# GEVCU-4.net
KiCad netlist of a schematic drawn in EAGLE
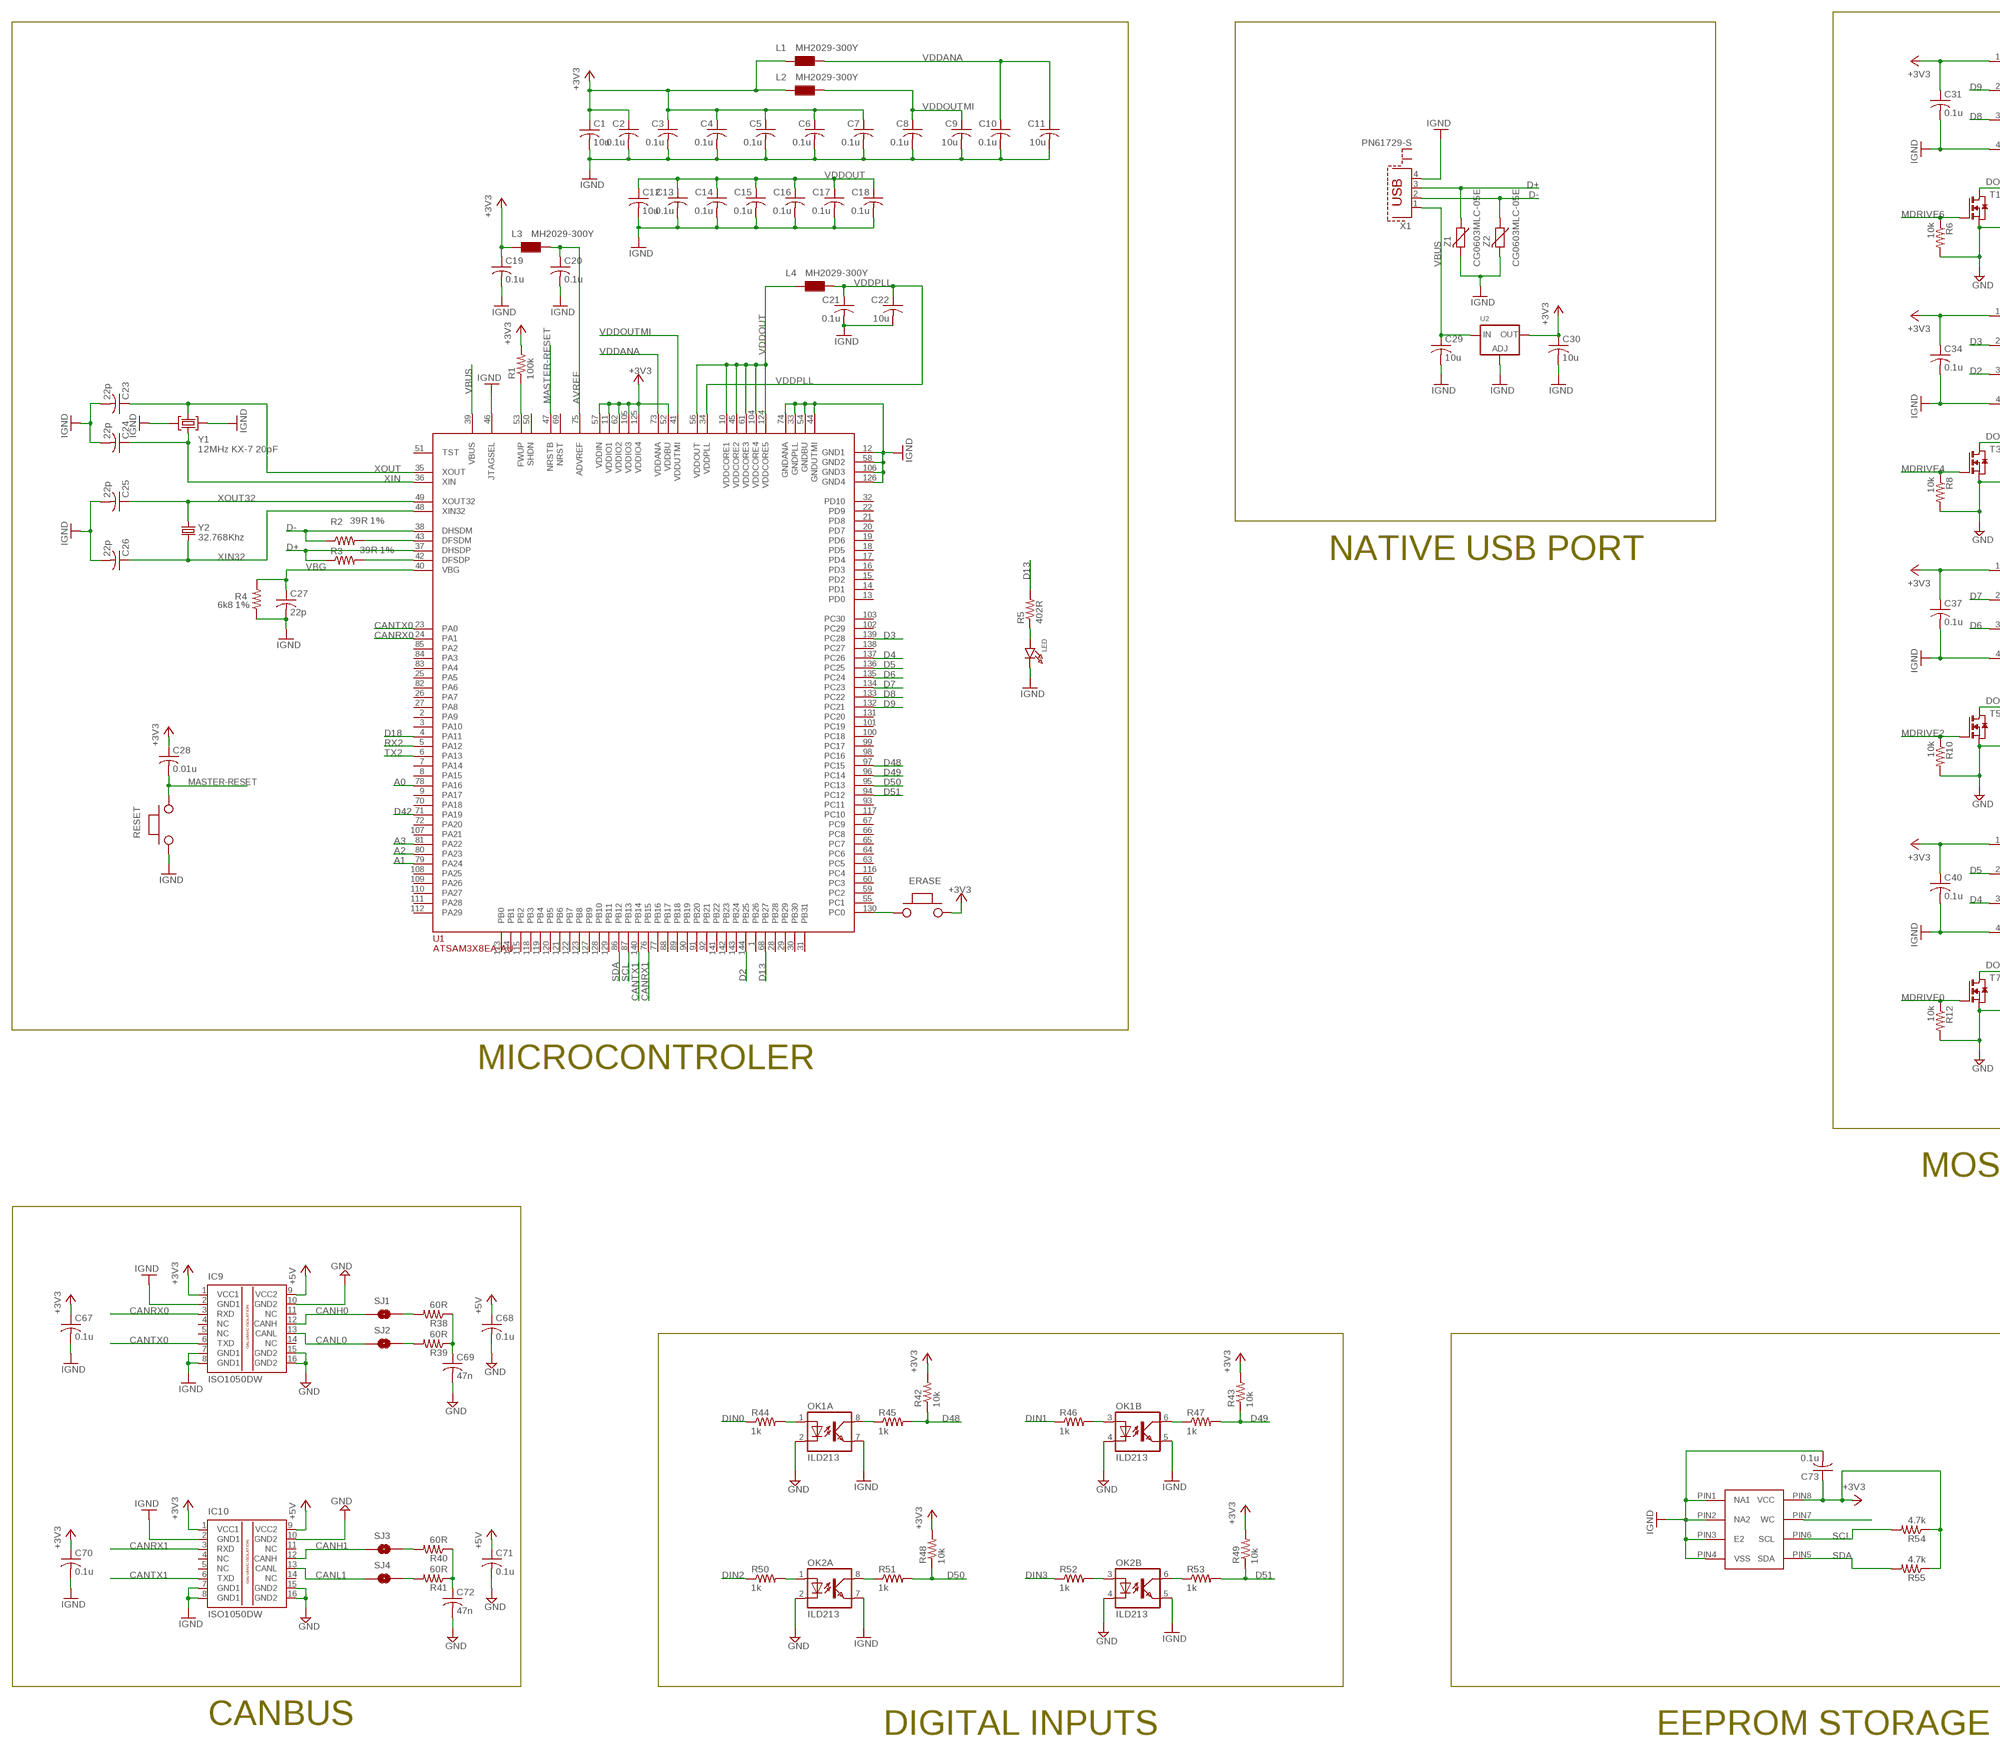
[diagram p0: schematic, sheet 1, part 1 of 2]
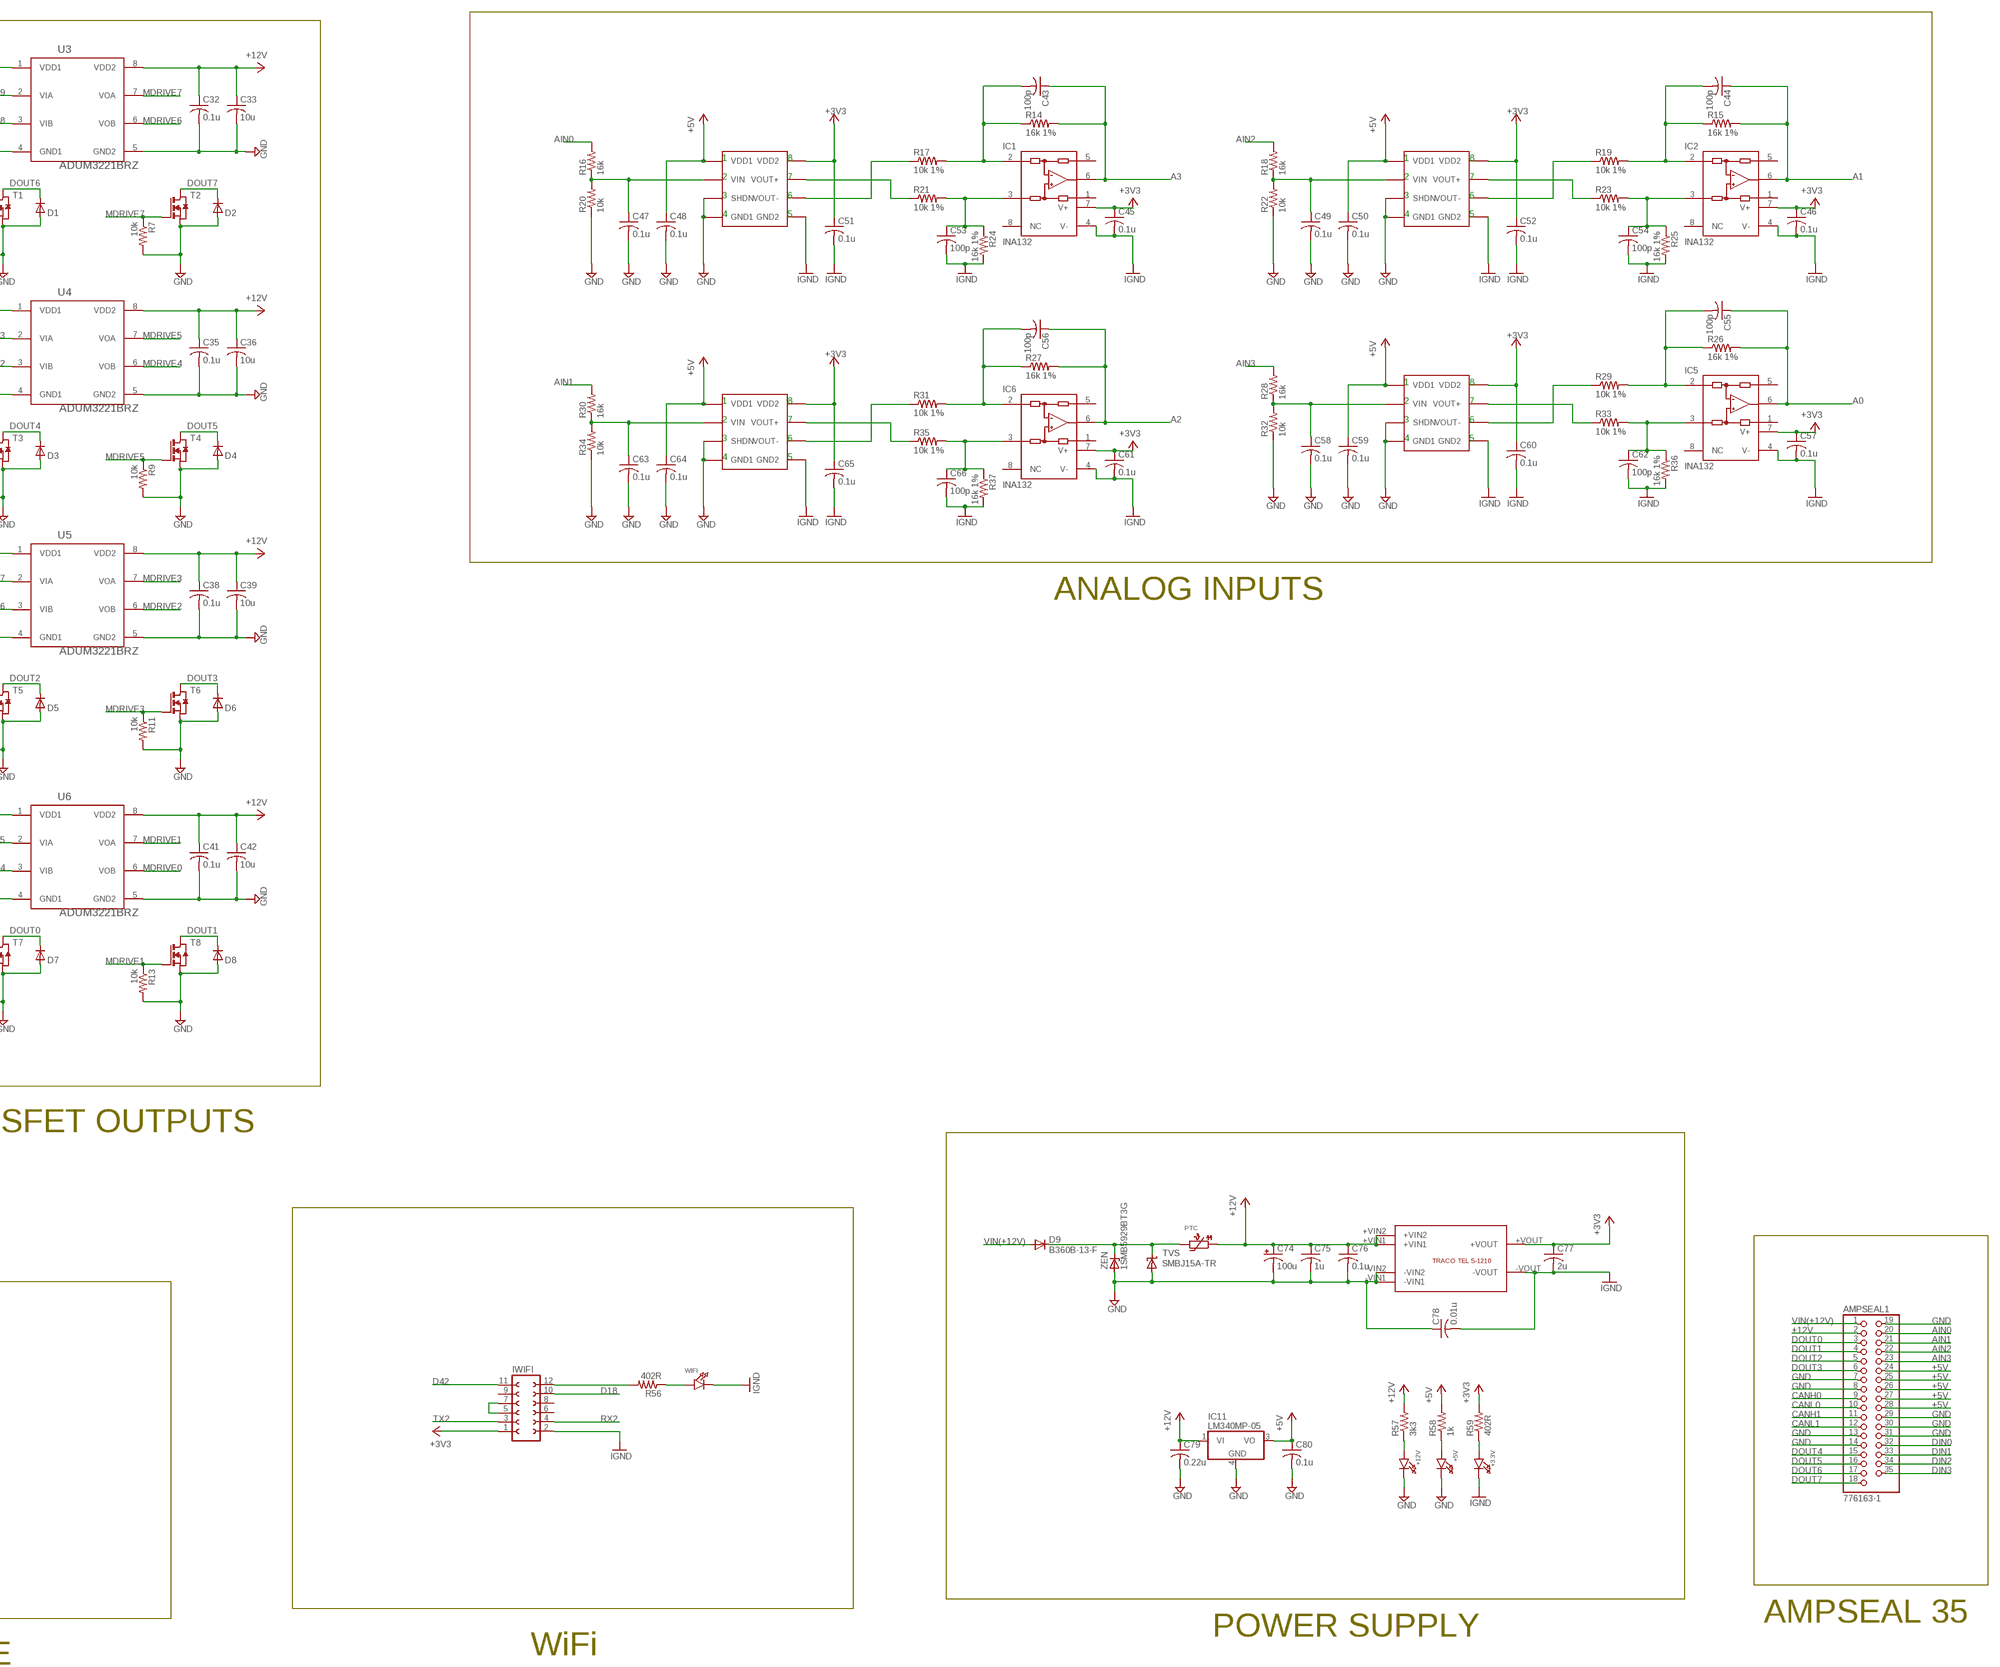
[diagram p1: schematic, sheet 1, part 2 of 2]

(export (version "E")
  (design (tool "Eeschema 10.0.6"))
  (components
    (comp (ref "+3.3V")
      (value "LED0805")
      (footprint "eagle-import:CHIPLED_0805")
      (libsource (lib "eagle-import") (part "LED0805"))
    )
    (comp (ref "+5V")
      (value "LED0805")
      (footprint "eagle-import:CHIPLED_0805")
      (libsource (lib "eagle-import") (part "LED0805"))
    )
    (comp (ref "+12V")
      (value "LED0805")
      (footprint "eagle-import:CHIPLED_0805")
      (libsource (lib "eagle-import") (part "LED0805"))
    )
    (comp (ref "AMPSEAL1")
      (value "776163-1")
      (footprint "eagle-import:AMPSEAL35")
      (libsource (lib "eagle-import") (part "AMPSEAL35"))
    )
    (comp (ref "C1")
      (value "10u")
      (footprint "eagle-import:C0805")
      (libsource (lib "eagle-import") (part "C-USC0805"))
    )
    (comp (ref "C2")
      (value "0.1u")
      (footprint "eagle-import:C0805")
      (libsource (lib "eagle-import") (part "C-USC0805"))
    )
    (comp (ref "C3")
      (value "0.1u")
      (footprint "eagle-import:C0805")
      (libsource (lib "eagle-import") (part "C-USC0805"))
    )
    (comp (ref "C4")
      (value "0.1u")
      (footprint "eagle-import:C0805")
      (libsource (lib "eagle-import") (part "C-USC0805"))
    )
    (comp (ref "C5")
      (value "0.1u")
      (footprint "eagle-import:C0805")
      (libsource (lib "eagle-import") (part "C-USC0805"))
    )
    (comp (ref "C6")
      (value "0.1u")
      (footprint "eagle-import:C0805")
      (libsource (lib "eagle-import") (part "C-USC0805"))
    )
    (comp (ref "C7")
      (value "0.1u")
      (footprint "eagle-import:C0805")
      (libsource (lib "eagle-import") (part "C-USC0805"))
    )
    (comp (ref "C8")
      (value "0.1u")
      (footprint "eagle-import:C0805")
      (libsource (lib "eagle-import") (part "C-USC0805"))
    )
    (comp (ref "C9")
      (value "10u")
      (footprint "eagle-import:C0805")
      (libsource (lib "eagle-import") (part "C-USC0805"))
    )
    (comp (ref "C10")
      (value "0.1u")
      (footprint "eagle-import:C0805")
      (libsource (lib "eagle-import") (part "C-USC0805"))
    )
    (comp (ref "C11")
      (value "10u")
      (footprint "eagle-import:C0805")
      (libsource (lib "eagle-import") (part "C-USC0805"))
    )
    (comp (ref "C12")
      (value "10u")
      (footprint "eagle-import:C0805")
      (libsource (lib "eagle-import") (part "C-USC0805"))
    )
    (comp (ref "C13")
      (value "0.1u")
      (footprint "eagle-import:C0805")
      (libsource (lib "eagle-import") (part "C-USC0805"))
    )
    (comp (ref "C14")
      (value "0.1u")
      (footprint "eagle-import:C0805")
      (libsource (lib "eagle-import") (part "C-USC0805"))
    )
    (comp (ref "C15")
      (value "0.1u")
      (footprint "eagle-import:C0805")
      (libsource (lib "eagle-import") (part "C-USC0805"))
    )
    (comp (ref "C16")
      (value "0.1u")
      (footprint "eagle-import:C0805")
      (libsource (lib "eagle-import") (part "C-USC0805"))
    )
    (comp (ref "C17")
      (value "0.1u")
      (footprint "eagle-import:C0805")
      (libsource (lib "eagle-import") (part "C-USC0805"))
    )
    (comp (ref "C18")
      (value "0.1u")
      (footprint "eagle-import:C0805")
      (libsource (lib "eagle-import") (part "C-USC0805"))
    )
    (comp (ref "C19")
      (value "0.1u")
      (footprint "eagle-import:C0805")
      (libsource (lib "eagle-import") (part "C-USC0805"))
    )
    (comp (ref "C20")
      (value "0.1u")
      (footprint "eagle-import:C0805")
      (libsource (lib "eagle-import") (part "C-USC0805"))
    )
    (comp (ref "C21")
      (value "0.1u")
      (footprint "eagle-import:C0805")
      (libsource (lib "eagle-import") (part "C-USC0805"))
    )
    (comp (ref "C22")
      (value "10u")
      (footprint "eagle-import:C0805")
      (libsource (lib "eagle-import") (part "C-USC0805"))
    )
    (comp (ref "C23")
      (value "22p")
      (footprint "eagle-import:C1206")
      (libsource (lib "eagle-import") (part "C-USC1206"))
    )
    (comp (ref "C24")
      (value "22p")
      (footprint "eagle-import:C1206")
      (libsource (lib "eagle-import") (part "C-USC1206"))
    )
    (comp (ref "C25")
      (value "22p")
      (footprint "eagle-import:C0805")
      (libsource (lib "eagle-import") (part "C-USC0805"))
    )
    (comp (ref "C26")
      (value "22p")
      (footprint "eagle-import:C0805")
      (libsource (lib "eagle-import") (part "C-USC0805"))
    )
    (comp (ref "C27")
      (value "22p")
      (footprint "eagle-import:C0805")
      (libsource (lib "eagle-import") (part "C-USC0805"))
    )
    (comp (ref "C28")
      (value "0.01u")
      (footprint "eagle-import:C0805")
      (libsource (lib "eagle-import") (part "C-USC0805"))
    )
    (comp (ref "C29")
      (value "10u")
      (footprint "eagle-import:C0805")
      (libsource (lib "eagle-import") (part "C-USC0805"))
    )
    (comp (ref "C30")
      (value "10u")
      (footprint "eagle-import:C0805")
      (libsource (lib "eagle-import") (part "C-USC0805"))
    )
    (comp (ref "C31")
      (value "0.1u")
      (footprint "eagle-import:C0805")
      (libsource (lib "eagle-import") (part "C-USC0805"))
    )
    (comp (ref "C32")
      (value "0.1u")
      (footprint "eagle-import:C0805")
      (libsource (lib "eagle-import") (part "C-USC0805"))
    )
    (comp (ref "C33")
      (value "10u")
      (footprint "eagle-import:C0805")
      (libsource (lib "eagle-import") (part "C-USC0805"))
    )
    (comp (ref "C34")
      (value "0.1u")
      (footprint "eagle-import:C0805")
      (libsource (lib "eagle-import") (part "C-USC0805"))
    )
    (comp (ref "C35")
      (value "0.1u")
      (footprint "eagle-import:C0805")
      (libsource (lib "eagle-import") (part "C-USC0805"))
    )
    (comp (ref "C36")
      (value "10u")
      (footprint "eagle-import:C0805")
      (libsource (lib "eagle-import") (part "C-USC0805"))
    )
    (comp (ref "C37")
      (value "0.1u")
      (footprint "eagle-import:C0805")
      (libsource (lib "eagle-import") (part "C-USC0805"))
    )
    (comp (ref "C38")
      (value "0.1u")
      (footprint "eagle-import:C0805")
      (libsource (lib "eagle-import") (part "C-USC0805"))
    )
    (comp (ref "C39")
      (value "10u")
      (footprint "eagle-import:C0805")
      (libsource (lib "eagle-import") (part "C-USC0805"))
    )
    (comp (ref "C40")
      (value "0.1u")
      (footprint "eagle-import:C0805")
      (libsource (lib "eagle-import") (part "C-USC0805"))
    )
    (comp (ref "C41")
      (value "0.1u")
      (footprint "eagle-import:C0805")
      (libsource (lib "eagle-import") (part "C-USC0805"))
    )
    (comp (ref "C42")
      (value "10u")
      (footprint "eagle-import:C0805")
      (libsource (lib "eagle-import") (part "C-USC0805"))
    )
    (comp (ref "C43")
      (value "100p")
      (footprint "eagle-import:C0805")
      (libsource (lib "eagle-import") (part "C-USC0805"))
    )
    (comp (ref "C44")
      (value "100p")
      (footprint "eagle-import:C0805")
      (libsource (lib "eagle-import") (part "C-USC0805"))
    )
    (comp (ref "C45")
      (value "0.1u")
      (footprint "eagle-import:C0805")
      (libsource (lib "eagle-import") (part "C-USC0805"))
    )
    (comp (ref "C46")
      (value "0.1u")
      (footprint "eagle-import:C0805")
      (libsource (lib "eagle-import") (part "C-USC0805"))
    )
    (comp (ref "C47")
      (value "0.1u")
      (footprint "eagle-import:C0805")
      (libsource (lib "eagle-import") (part "C-USC0805"))
    )
    (comp (ref "C48")
      (value "0.1u")
      (footprint "eagle-import:C1206")
      (libsource (lib "eagle-import") (part "C-USC1206"))
    )
    (comp (ref "C49")
      (value "0.1u")
      (footprint "eagle-import:C0805")
      (libsource (lib "eagle-import") (part "C-USC0805"))
    )
    (comp (ref "C50")
      (value "0.1u")
      (footprint "eagle-import:C1206")
      (libsource (lib "eagle-import") (part "C-USC1206"))
    )
    (comp (ref "C51")
      (value "0.1u")
      (footprint "eagle-import:C0805")
      (libsource (lib "eagle-import") (part "C-USC0805"))
    )
    (comp (ref "C52")
      (value "0.1u")
      (footprint "eagle-import:C0805")
      (libsource (lib "eagle-import") (part "C-USC0805"))
    )
    (comp (ref "C53")
      (value "100p")
      (footprint "eagle-import:C0805")
      (libsource (lib "eagle-import") (part "C-USC0805"))
    )
    (comp (ref "C54")
      (value "100p")
      (footprint "eagle-import:C0805")
      (libsource (lib "eagle-import") (part "C-USC0805"))
    )
    (comp (ref "C55")
      (value "100p")
      (footprint "eagle-import:C0805")
      (libsource (lib "eagle-import") (part "C-USC0805"))
    )
    (comp (ref "C56")
      (value "100p")
      (footprint "eagle-import:C0805")
      (libsource (lib "eagle-import") (part "C-USC0805"))
    )
    (comp (ref "C57")
      (value "0.1u")
      (footprint "eagle-import:C0805")
      (libsource (lib "eagle-import") (part "C-USC0805"))
    )
    (comp (ref "C58")
      (value "0.1u")
      (footprint "eagle-import:C0805")
      (libsource (lib "eagle-import") (part "C-USC0805"))
    )
    (comp (ref "C59")
      (value "0.1u")
      (footprint "eagle-import:C1206")
      (libsource (lib "eagle-import") (part "C-USC1206"))
    )
    (comp (ref "C60")
      (value "0.1u")
      (footprint "eagle-import:C0805")
      (libsource (lib "eagle-import") (part "C-USC0805"))
    )
    (comp (ref "C61")
      (value "0.1u")
      (footprint "eagle-import:C0805")
      (libsource (lib "eagle-import") (part "C-USC0805"))
    )
    (comp (ref "C62")
      (value "100p")
      (footprint "eagle-import:C0805")
      (libsource (lib "eagle-import") (part "C-USC0805"))
    )
    (comp (ref "C63")
      (value "0.1u")
      (footprint "eagle-import:C0805")
      (libsource (lib "eagle-import") (part "C-USC0805"))
    )
    (comp (ref "C64")
      (value "0.1u")
      (footprint "eagle-import:C1206")
      (libsource (lib "eagle-import") (part "C-USC1206"))
    )
    (comp (ref "C65")
      (value "0.1u")
      (footprint "eagle-import:C0805")
      (libsource (lib "eagle-import") (part "C-USC0805"))
    )
    (comp (ref "C66")
      (value "100p")
      (footprint "eagle-import:C0805")
      (libsource (lib "eagle-import") (part "C-USC0805"))
    )
    (comp (ref "C67")
      (value "0.1u")
      (footprint "eagle-import:C0805")
      (libsource (lib "eagle-import") (part "C-USC0805"))
    )
    (comp (ref "C68")
      (value "0.1u")
      (footprint "eagle-import:C0805")
      (libsource (lib "eagle-import") (part "C-USC0805"))
    )
    (comp (ref "C69")
      (value "47n")
      (footprint "eagle-import:C0805")
      (libsource (lib "eagle-import") (part "C-USC0805"))
    )
    (comp (ref "C70")
      (value "0.1u")
      (footprint "eagle-import:C0805")
      (libsource (lib "eagle-import") (part "C-USC0805"))
    )
    (comp (ref "C71")
      (value "0.1u")
      (footprint "eagle-import:C0805")
      (libsource (lib "eagle-import") (part "C-USC0805"))
    )
    (comp (ref "C72")
      (value "47n")
      (footprint "eagle-import:C0805")
      (libsource (lib "eagle-import") (part "C-USC0805"))
    )
    (comp (ref "C73")
      (value "0.1u")
      (footprint "eagle-import:C0805")
      (libsource (lib "eagle-import") (part "C-USC0805"))
    )
    (comp (ref "C74")
      (value "100u")
      (footprint "eagle-import:E2,5-6")
      (libsource (lib "eagle-import") (part "CPOL-USE2.5-6"))
    )
    (comp (ref "C75")
      (value "1u")
      (footprint "eagle-import:C0805")
      (libsource (lib "eagle-import") (part "C-USC0805"))
    )
    (comp (ref "C76")
      (value "0.1u")
      (footprint "eagle-import:C0805")
      (libsource (lib "eagle-import") (part "C-USC0805"))
    )
    (comp (ref "C77")
      (value "2u")
      (footprint "eagle-import:C0805")
      (libsource (lib "eagle-import") (part "C-USC0805"))
    )
    (comp (ref "C78")
      (value "0.01u")
      (footprint "eagle-import:C1812")
      (libsource (lib "eagle-import") (part "C-USC1812"))
    )
    (comp (ref "C79")
      (value "0.22u")
      (footprint "eagle-import:C0805")
      (libsource (lib "eagle-import") (part "C-USC0805"))
    )
    (comp (ref "C80")
      (value "0.1u")
      (footprint "eagle-import:C0805")
      (libsource (lib "eagle-import") (part "C-USC0805"))
    )
    (comp (ref "D1")
      (value "MBR0520LT")
      (footprint "eagle-import:SOD123")
      (libsource (lib "eagle-import") (part "MBR0520LT"))
    )
    (comp (ref "D2")
      (value "MBR0520LT")
      (footprint "eagle-import:SOD123")
      (libsource (lib "eagle-import") (part "MBR0520LT"))
    )
    (comp (ref "D3")
      (value "MBR0520LT")
      (footprint "eagle-import:SOD123")
      (libsource (lib "eagle-import") (part "MBR0520LT"))
    )
    (comp (ref "D4")
      (value "MBR0520LT")
      (footprint "eagle-import:SOD123")
      (libsource (lib "eagle-import") (part "MBR0520LT"))
    )
    (comp (ref "D5")
      (value "MBR0520LT")
      (footprint "eagle-import:SOD123")
      (libsource (lib "eagle-import") (part "MBR0520LT"))
    )
    (comp (ref "D6")
      (value "MBR0520LT")
      (footprint "eagle-import:SOD123")
      (libsource (lib "eagle-import") (part "MBR0520LT"))
    )
    (comp (ref "D7")
      (value "MBR0520LT")
      (footprint "eagle-import:SOD123")
      (libsource (lib "eagle-import") (part "MBR0520LT"))
    )
    (comp (ref "D8")
      (value "MBR0520LT")
      (footprint "eagle-import:SOD123")
      (libsource (lib "eagle-import") (part "MBR0520LT"))
    )
    (comp (ref "D9")
      (value "B360B-13-F")
      (footprint "eagle-import:SMB")
      (libsource (lib "eagle-import") (part "DIODE-SMB"))
    )
    (comp (ref "ERASE")
      (value "PUCHBUTTON")
      (footprint "eagle-import:PUCHBUTTON")
      (libsource (lib "eagle-import") (part "PUCHBUTTON"))
    )
    (comp (ref "IC1")
      (value "INA132")
      (footprint "eagle-import:SO08")
      (fields (field (name "MF") "TEXAS INSTRUMENTS") (field (name "MPN") "INA105KU"))
      (libsource (lib "eagle-import") (part "INA105U"))
    )
    (comp (ref "IC2")
      (value "INA132")
      (footprint "eagle-import:SO08")
      (fields (field (name "MF") "TEXAS INSTRUMENTS") (field (name "MPN") "INA105KU"))
      (libsource (lib "eagle-import") (part "INA105U"))
    )
    (comp (ref "IC3")
      (value "CK_CUSTOM_ACPL-C87A-000E")
      (footprint "eagle-import:CK_CUSTOM_SO8-WIDE")
      (libsource (lib "eagle-import") (part "CK_CUSTOM_ACPL-C87A-000E"))
    )
    (comp (ref "IC4")
      (value "CK_CUSTOM_ACPL-C87A-000E")
      (footprint "eagle-import:CK_CUSTOM_SO8-WIDE")
      (libsource (lib "eagle-import") (part "CK_CUSTOM_ACPL-C87A-000E"))
    )
    (comp (ref "IC5")
      (value "INA132")
      (footprint "eagle-import:SO08")
      (fields (field (name "MF") "TEXAS INSTRUMENTS") (field (name "MPN") "INA105KU"))
      (libsource (lib "eagle-import") (part "INA105U"))
    )
    (comp (ref "IC6")
      (value "INA132")
      (footprint "eagle-import:SO08")
      (fields (field (name "MF") "TEXAS INSTRUMENTS") (field (name "MPN") "INA105KU"))
      (libsource (lib "eagle-import") (part "INA105U"))
    )
    (comp (ref "IC7")
      (value "CK_CUSTOM_ACPL-C87A-000E")
      (footprint "eagle-import:CK_CUSTOM_SO8-WIDE")
      (libsource (lib "eagle-import") (part "CK_CUSTOM_ACPL-C87A-000E"))
    )
    (comp (ref "IC8")
      (value "CK_CUSTOM_ACPL-C87A-000E")
      (footprint "eagle-import:CK_CUSTOM_SO8-WIDE")
      (libsource (lib "eagle-import") (part "CK_CUSTOM_ACPL-C87A-000E"))
    )
    (comp (ref "IC9")
      (value "ISO1050DW")
      (footprint "eagle-import:DUB-R-PDSO-G8")
      (libsource (lib "eagle-import") (part "ISO1050DUB"))
    )
    (comp (ref "IC10")
      (value "ISO1050DW")
      (footprint "eagle-import:DUB-R-PDSO-G8")
      (libsource (lib "eagle-import") (part "ISO1050DUB"))
    )
    (comp (ref "IC11")
      (value "LM340MP-05")
      (footprint "eagle-import:SOT223")
      (libsource (lib "eagle-import") (part "LM340?-MP05"))
    )
    (comp (ref "IWIFI")
      (value "FE06-2")
      (footprint "eagle-import:FE06-2")
      (libsource (lib "eagle-import") (part "FE06-2"))
    )
    (comp (ref "L1")
      (value "MH2029-300Y")
      (footprint "eagle-import:0805")
      (libsource (lib "eagle-import") (part "WE-CBF_0805"))
    )
    (comp (ref "L2")
      (value "MH2029-300Y")
      (footprint "eagle-import:0805")
      (libsource (lib "eagle-import") (part "WE-CBF_0805"))
    )
    (comp (ref "L3")
      (value "MH2029-300Y")
      (footprint "eagle-import:0805")
      (libsource (lib "eagle-import") (part "WE-CBF_0805"))
    )
    (comp (ref "L4")
      (value "MH2029-300Y")
      (footprint "eagle-import:0805")
      (libsource (lib "eagle-import") (part "WE-CBF_0805"))
    )
    (comp (ref "LED")
      (value "LED0805")
      (footprint "eagle-import:CHIPLED_0805")
      (libsource (lib "eagle-import") (part "LED0805"))
    )
    (comp (ref "OK1")
      (value "ILD213")
      (footprint "eagle-import:SOIC08")
      (fields (field (name "MF") "VISHAY/TELEFUNKEN") (field (name "MPN") "ILD213T"))
      (libsource (lib "eagle-import") (part "ILD213"))
    )
    (comp (ref "OK2")
      (value "ILD213")
      (footprint "eagle-import:SOIC08")
      (fields (field (name "MF") "VISHAY/TELEFUNKEN") (field (name "MPN") "ILD213T"))
      (libsource (lib "eagle-import") (part "ILD213"))
    )
    (comp (ref "PTC")
      (value "PTC1812")
      (footprint "eagle-import:PTC1812")
      (libsource (lib "eagle-import") (part "PTC1812"))
    )
    (comp (ref "R1")
      (value "100k")
      (footprint "eagle-import:R0805")
      (libsource (lib "eagle-import") (part "R-US_R0805"))
    )
    (comp (ref "R2")
      (value "39R 1%")
      (footprint "eagle-import:R0805")
      (libsource (lib "eagle-import") (part "R-US_R0805"))
    )
    (comp (ref "R3")
      (value "39R 1%")
      (footprint "eagle-import:R0805")
      (libsource (lib "eagle-import") (part "R-US_R0805"))
    )
    (comp (ref "R4")
      (value "6k8 1%")
      (footprint "eagle-import:R0805")
      (libsource (lib "eagle-import") (part "R-US_R0805"))
    )
    (comp (ref "R5")
      (value "402R")
      (footprint "eagle-import:R0805")
      (libsource (lib "eagle-import") (part "R-US_R0805"))
    )
    (comp (ref "R6")
      (value "10k")
      (footprint "eagle-import:R0805")
      (libsource (lib "eagle-import") (part "R-US_R0805"))
    )
    (comp (ref "R7")
      (value "10k")
      (footprint "eagle-import:R0805")
      (libsource (lib "eagle-import") (part "R-US_R0805"))
    )
    (comp (ref "R8")
      (value "10k")
      (footprint "eagle-import:R0805")
      (libsource (lib "eagle-import") (part "R-US_R0805"))
    )
    (comp (ref "R9")
      (value "10k")
      (footprint "eagle-import:R0805")
      (libsource (lib "eagle-import") (part "R-US_R0805"))
    )
    (comp (ref "R10")
      (value "10k")
      (footprint "eagle-import:R0805")
      (libsource (lib "eagle-import") (part "R-US_R0805"))
    )
    (comp (ref "R11")
      (value "10k")
      (footprint "eagle-import:R0805")
      (libsource (lib "eagle-import") (part "R-US_R0805"))
    )
    (comp (ref "R12")
      (value "10k")
      (footprint "eagle-import:R0805")
      (libsource (lib "eagle-import") (part "R-US_R0805"))
    )
    (comp (ref "R13")
      (value "10k")
      (footprint "eagle-import:R0805")
      (libsource (lib "eagle-import") (part "R-US_R0805"))
    )
    (comp (ref "R14")
      (value "16k 1%")
      (footprint "eagle-import:R0805")
      (libsource (lib "eagle-import") (part "R-US_R0805"))
    )
    (comp (ref "R15")
      (value "16k 1%")
      (footprint "eagle-import:R0805")
      (libsource (lib "eagle-import") (part "R-US_R0805"))
    )
    (comp (ref "R16")
      (value "16k")
      (footprint "eagle-import:R0805")
      (libsource (lib "eagle-import") (part "R-US_R0805"))
    )
    (comp (ref "R17")
      (value "10k 1%")
      (footprint "eagle-import:R0805")
      (libsource (lib "eagle-import") (part "R-US_R0805"))
    )
    (comp (ref "R18")
      (value "16k")
      (footprint "eagle-import:R0805")
      (libsource (lib "eagle-import") (part "R-US_R0805"))
    )
    (comp (ref "R19")
      (value "10k 1%")
      (footprint "eagle-import:R0805")
      (libsource (lib "eagle-import") (part "R-US_R0805"))
    )
    (comp (ref "R20")
      (value "10k")
      (footprint "eagle-import:R0805")
      (libsource (lib "eagle-import") (part "R-US_R0805"))
    )
    (comp (ref "R21")
      (value "10k 1%")
      (footprint "eagle-import:R0805")
      (libsource (lib "eagle-import") (part "R-US_R0805"))
    )
    (comp (ref "R22")
      (value "10k")
      (footprint "eagle-import:R0805")
      (libsource (lib "eagle-import") (part "R-US_R0805"))
    )
    (comp (ref "R23")
      (value "10k 1%")
      (footprint "eagle-import:R0805")
      (libsource (lib "eagle-import") (part "R-US_R0805"))
    )
    (comp (ref "R24")
      (value "16k 1%")
      (footprint "eagle-import:R0805")
      (libsource (lib "eagle-import") (part "R-US_R0805"))
    )
    (comp (ref "R25")
      (value "16k 1%")
      (footprint "eagle-import:R0805")
      (libsource (lib "eagle-import") (part "R-US_R0805"))
    )
    (comp (ref "R26")
      (value "16k 1%")
      (footprint "eagle-import:R0805")
      (libsource (lib "eagle-import") (part "R-US_R0805"))
    )
    (comp (ref "R27")
      (value "16k 1%")
      (footprint "eagle-import:R0805")
      (libsource (lib "eagle-import") (part "R-US_R0805"))
    )
    (comp (ref "R28")
      (value "16k")
      (footprint "eagle-import:R0805")
      (libsource (lib "eagle-import") (part "R-US_R0805"))
    )
    (comp (ref "R29")
      (value "10k 1%")
      (footprint "eagle-import:R0805")
      (libsource (lib "eagle-import") (part "R-US_R0805"))
    )
    (comp (ref "R30")
      (value "16k")
      (footprint "eagle-import:R0805")
      (libsource (lib "eagle-import") (part "R-US_R0805"))
    )
    (comp (ref "R31")
      (value "10k 1%")
      (footprint "eagle-import:R0805")
      (libsource (lib "eagle-import") (part "R-US_R0805"))
    )
    (comp (ref "R32")
      (value "10k")
      (footprint "eagle-import:R0805")
      (libsource (lib "eagle-import") (part "R-US_R0805"))
    )
    (comp (ref "R33")
      (value "10k 1%")
      (footprint "eagle-import:R0805")
      (libsource (lib "eagle-import") (part "R-US_R0805"))
    )
    (comp (ref "R34")
      (value "10k")
      (footprint "eagle-import:R0805")
      (libsource (lib "eagle-import") (part "R-US_R0805"))
    )
    (comp (ref "R35")
      (value "10k 1%")
      (footprint "eagle-import:R0805")
      (libsource (lib "eagle-import") (part "R-US_R0805"))
    )
    (comp (ref "R36")
      (value "16k 1%")
      (footprint "eagle-import:R0805")
      (libsource (lib "eagle-import") (part "R-US_R0805"))
    )
    (comp (ref "R37")
      (value "16k 1%")
      (footprint "eagle-import:R0805")
      (libsource (lib "eagle-import") (part "R-US_R0805"))
    )
    (comp (ref "R38")
      (value "60R")
      (footprint "eagle-import:R0805")
      (libsource (lib "eagle-import") (part "R-US_R0805"))
    )
    (comp (ref "R39")
      (value "60R")
      (footprint "eagle-import:R0805")
      (libsource (lib "eagle-import") (part "R-US_R0805"))
    )
    (comp (ref "R40")
      (value "60R")
      (footprint "eagle-import:R0805")
      (libsource (lib "eagle-import") (part "R-US_R0805"))
    )
    (comp (ref "R41")
      (value "60R")
      (footprint "eagle-import:R0805")
      (libsource (lib "eagle-import") (part "R-US_R0805"))
    )
    (comp (ref "R42")
      (value "10k")
      (footprint "eagle-import:R0805")
      (libsource (lib "eagle-import") (part "R-US_R0805"))
    )
    (comp (ref "R43")
      (value "10k")
      (footprint "eagle-import:R0805")
      (libsource (lib "eagle-import") (part "R-US_R0805"))
    )
    (comp (ref "R44")
      (value "1k")
      (footprint "eagle-import:R0805")
      (libsource (lib "eagle-import") (part "R-US_R0805"))
    )
    (comp (ref "R45")
      (value "1k")
      (footprint "eagle-import:R0805")
      (libsource (lib "eagle-import") (part "R-US_R0805"))
    )
    (comp (ref "R46")
      (value "1k")
      (footprint "eagle-import:R0805")
      (libsource (lib "eagle-import") (part "R-US_R0805"))
    )
    (comp (ref "R47")
      (value "1k")
      (footprint "eagle-import:R0805")
      (libsource (lib "eagle-import") (part "R-US_R0805"))
    )
    (comp (ref "R48")
      (value "10k")
      (footprint "eagle-import:R0805")
      (libsource (lib "eagle-import") (part "R-US_R0805"))
    )
    (comp (ref "R49")
      (value "10k")
      (footprint "eagle-import:R0805")
      (libsource (lib "eagle-import") (part "R-US_R0805"))
    )
    (comp (ref "R50")
      (value "1k")
      (footprint "eagle-import:R0805")
      (libsource (lib "eagle-import") (part "R-US_R0805"))
    )
    (comp (ref "R51")
      (value "1k")
      (footprint "eagle-import:R0805")
      (libsource (lib "eagle-import") (part "R-US_R0805"))
    )
    (comp (ref "R52")
      (value "1k")
      (footprint "eagle-import:R0805")
      (libsource (lib "eagle-import") (part "R-US_R0805"))
    )
    (comp (ref "R53")
      (value "1k")
      (footprint "eagle-import:R0805")
      (libsource (lib "eagle-import") (part "R-US_R0805"))
    )
    (comp (ref "R54")
      (value "4.7k")
      (footprint "eagle-import:R0805")
      (libsource (lib "eagle-import") (part "R-US_R0805"))
    )
    (comp (ref "R55")
      (value "4.7k")
      (footprint "eagle-import:R0805")
      (libsource (lib "eagle-import") (part "R-US_R0805"))
    )
    (comp (ref "R56")
      (value "402R")
      (footprint "eagle-import:R0805")
      (libsource (lib "eagle-import") (part "R-US_R0805"))
    )
    (comp (ref "R57")
      (value "3k3")
      (footprint "eagle-import:R0805")
      (libsource (lib "eagle-import") (part "R-US_R0805"))
    )
    (comp (ref "R58")
      (value "1k")
      (footprint "eagle-import:R0805")
      (libsource (lib "eagle-import") (part "R-US_R0805"))
    )
    (comp (ref "R59")
      (value "402R")
      (footprint "eagle-import:R0805")
      (libsource (lib "eagle-import") (part "R-US_R0805"))
    )
    (comp (ref "RESET")
      (value "PUCHBUTTON")
      (footprint "eagle-import:PUCHBUTTON")
      (libsource (lib "eagle-import") (part "PUCHBUTTON"))
    )
    (comp (ref "SJ1")
      (value "SOLDERJUMPERNO")
      (footprint "eagle-import:SJ_2S-NO")
      (libsource (lib "eagle-import") (part "SOLDERJUMPERNO"))
    )
    (comp (ref "SJ2")
      (value "SOLDERJUMPERNO")
      (footprint "eagle-import:SJ_2S-NO")
      (libsource (lib "eagle-import") (part "SOLDERJUMPERNO"))
    )
    (comp (ref "SJ3")
      (value "SOLDERJUMPERNO")
      (footprint "eagle-import:SJ_2S-NO")
      (libsource (lib "eagle-import") (part "SOLDERJUMPERNO"))
    )
    (comp (ref "SJ4")
      (value "SOLDERJUMPERNO")
      (footprint "eagle-import:SJ_2S-NO")
      (libsource (lib "eagle-import") (part "SOLDERJUMPERNO"))
    )
    (comp (ref "T1")
      (value "NMOSSOT223")
      (footprint "eagle-import:SOT223")
      (libsource (lib "eagle-import") (part "NMOSSOT223"))
    )
    (comp (ref "T2")
      (value "NMOSSOT223")
      (footprint "eagle-import:SOT223")
      (libsource (lib "eagle-import") (part "NMOSSOT223"))
    )
    (comp (ref "T3")
      (value "NMOSSOT223")
      (footprint "eagle-import:SOT223")
      (libsource (lib "eagle-import") (part "NMOSSOT223"))
    )
    (comp (ref "T4")
      (value "NMOSSOT223")
      (footprint "eagle-import:SOT223")
      (libsource (lib "eagle-import") (part "NMOSSOT223"))
    )
    (comp (ref "T5")
      (value "NMOSSOT223")
      (footprint "eagle-import:SOT223")
      (libsource (lib "eagle-import") (part "NMOSSOT223"))
    )
    (comp (ref "T6")
      (value "NMOSSOT223")
      (footprint "eagle-import:SOT223")
      (libsource (lib "eagle-import") (part "NMOSSOT223"))
    )
    (comp (ref "T7")
      (value "NMOSSOT223")
      (footprint "eagle-import:SOT223")
      (libsource (lib "eagle-import") (part "NMOSSOT223"))
    )
    (comp (ref "T8")
      (value "NMOSSOT223")
      (footprint "eagle-import:SOT223")
      (libsource (lib "eagle-import") (part "NMOSSOT223"))
    )
    (comp (ref "TVS")
      (value "SMBJ15A-TR")
      (footprint "eagle-import:SMBJ")
      (libsource (lib "eagle-import") (part "SUPPRESSOR-SMBJ"))
    )
    (comp (ref "U1")
      (value "ATSAM3X8EA-AU")
      (footprint "eagle-import:LQFP144")
      (libsource (lib "eagle-import") (part "ATSAM3X/AAU"))
    )
    (comp (ref "U2")
      (value "LM1117SOT223-WAVE")
      (footprint "eagle-import:SOT223-W")
      (libsource (lib "eagle-import") (part "LM1117SOT223-WAVE"))
    )
    (comp (ref "U3")
      (value "ADUM3221BRZ")
      (footprint "eagle-import:SOIC127P600X175-8N")
      (libsource (lib "eagle-import") (part "ADUM3221BRZ"))
    )
    (comp (ref "U4")
      (value "ADUM3221BRZ")
      (footprint "eagle-import:SOIC127P600X175-8N")
      (libsource (lib "eagle-import") (part "ADUM3221BRZ"))
    )
    (comp (ref "U5")
      (value "ADUM3221BRZ")
      (footprint "eagle-import:SOIC127P600X175-8N")
      (libsource (lib "eagle-import") (part "ADUM3221BRZ"))
    )
    (comp (ref "U6")
      (value "ADUM3221BRZ")
      (footprint "eagle-import:SOIC127P600X175-8N")
      (libsource (lib "eagle-import") (part "ADUM3221BRZ"))
    )
    (comp (ref "U7")
      (value "CK_CUSTOM_M24M02-DRMN6TP")
      (footprint "eagle-import:CK_CUSTOM_SOIC8")
      (libsource (lib "eagle-import") (part "CK_CUSTOM_M24M02-DRMN6TP"))
    )
    (comp (ref "U8")
      (value "TRACO")
      (footprint "eagle-import:TRACO")
      (libsource (lib "eagle-import") (part "TRACO"))
    )
    (comp (ref "WIFI")
      (value "LED0805")
      (footprint "eagle-import:CHIPLED_0805")
      (libsource (lib "eagle-import") (part "LED0805"))
    )
    (comp (ref "X1")
      (value "PN61729-S")
      (footprint "eagle-import:PN61729-S")
      (libsource (lib "eagle-import") (part "PN61729-S"))
    )
    (comp (ref "Y1")
      (value "12MHz KX-7 20pF")
      (footprint "eagle-import:CRYSTAL-3.2-2.5")
      (libsource (lib "eagle-import") (part "CRYSTAL-3.2-2.5"))
    )
    (comp (ref "Y2")
      (value "32.768Khz")
      (footprint "eagle-import:RESONATOR_EPSON_FC_145")
      (libsource (lib "eagle-import") (part "RESONATOR_EPSON_FC_145"))
    )
    (comp (ref "Z1")
      (value "CG0603MLC-05E")
      (footprint "eagle-import:CT_CN0603")
      (libsource (lib "eagle-import") (part "VARISTORCN0603"))
    )
    (comp (ref "Z2")
      (value "CG0603MLC-05E")
      (footprint "eagle-import:CT_CN0603")
      (libsource (lib "eagle-import") (part "VARISTORCN0603"))
    )
    (comp (ref "ZEN")
      (value "1SMB5929BT3G")
      (footprint "eagle-import:SMB")
      (libsource (lib "eagle-import") (part "ZENER-DIODESMB"))
    )
  )
  (nets
    (net (code "1") (name "+3V3") (class "Default")
      (node (ref "C1") (pin "1") (pinfunction "1_1") (pintype "passive"))
      (node (ref "C19") (pin "1") (pinfunction "1_1") (pintype "passive"))
      (node (ref "C2") (pin "1") (pinfunction "1_1") (pintype "passive"))
      (node (ref "C28") (pin "1") (pinfunction "1_1") (pintype "passive"))
      (node (ref "C3") (pin "1") (pinfunction "1_1") (pintype "passive"))
      (node (ref "C30") (pin "1") (pinfunction "1_1") (pintype "passive"))
      (node (ref "C31") (pin "1") (pinfunction "1_1") (pintype "passive"))
      (node (ref "C34") (pin "1") (pinfunction "1_1") (pintype "passive"))
      (node (ref "C37") (pin "1") (pinfunction "1_1") (pintype "passive"))
      (node (ref "C4") (pin "1") (pinfunction "1_1") (pintype "passive"))
      (node (ref "C40") (pin "1") (pinfunction "1_1") (pintype "passive"))
      (node (ref "C45") (pin "1") (pinfunction "1_1") (pintype "passive"))
      (node (ref "C46") (pin "1") (pinfunction "1_1") (pintype "passive"))
      (node (ref "C5") (pin "1") (pinfunction "1_1") (pintype "passive"))
      (node (ref "C51") (pin "1") (pinfunction "1_1") (pintype "passive"))
      (node (ref "C52") (pin "1") (pinfunction "1_1") (pintype "passive"))
      (node (ref "C57") (pin "1") (pinfunction "1_1") (pintype "passive"))
      (node (ref "C6") (pin "1") (pinfunction "1_1") (pintype "passive"))
      (node (ref "C60") (pin "1") (pinfunction "1_1") (pintype "passive"))
      (node (ref "C61") (pin "1") (pinfunction "1_1") (pintype "passive"))
      (node (ref "C65") (pin "1") (pinfunction "1_1") (pintype "passive"))
      (node (ref "C67") (pin "1") (pinfunction "1_1") (pintype "passive"))
      (node (ref "C7") (pin "1") (pinfunction "1_1") (pintype "passive"))
      (node (ref "C70") (pin "1") (pinfunction "1_1") (pintype "passive"))
      (node (ref "C73") (pin "1") (pinfunction "1_1") (pintype "passive"))
      (node (ref "C77") (pin "1") (pinfunction "1_1") (pintype "passive"))
      (node (ref "ERASE") (pin "P$2") (pinfunction "P$5_P$2") (pintype "bidirectional"))
      (node (ref "IC1") (pin "7") (pinfunction "V+_7") (pintype "power_in"))
      (node (ref "IC10") (pin "1") (pinfunction "VCC1_1") (pintype "input"))
      (node (ref "IC2") (pin "7") (pinfunction "V+_7") (pintype "power_in"))
      (node (ref "IC3") (pin "8") (pinfunction "VDD2_8") (pintype "bidirectional"))
      (node (ref "IC4") (pin "8") (pinfunction "VDD2_8") (pintype "bidirectional"))
      (node (ref "IC5") (pin "7") (pinfunction "V+_7") (pintype "power_in"))
      (node (ref "IC6") (pin "7") (pinfunction "V+_7") (pintype "power_in"))
      (node (ref "IC7") (pin "8") (pinfunction "VDD2_8") (pintype "bidirectional"))
      (node (ref "IC8") (pin "8") (pinfunction "VDD2_8") (pintype "bidirectional"))
      (node (ref "IC9") (pin "1") (pinfunction "VCC1_1") (pintype "input"))
      (node (ref "IWIFI") (pin "1") (pinfunction "1_1") (pintype "passive"))
      (node (ref "L1") (pin "1") (pinfunction "1_1") (pintype "passive"))
      (node (ref "L2") (pin "1") (pinfunction "1_1") (pintype "passive"))
      (node (ref "L3") (pin "1") (pinfunction "1_1") (pintype "passive"))
      (node (ref "R1") (pin "2") (pinfunction "2_2") (pintype "passive"))
      (node (ref "R42") (pin "2") (pinfunction "2_2") (pintype "passive"))
      (node (ref "R43") (pin "2") (pinfunction "2_2") (pintype "passive"))
      (node (ref "R48") (pin "2") (pinfunction "2_2") (pintype "passive"))
      (node (ref "R49") (pin "2") (pinfunction "2_2") (pintype "passive"))
      (node (ref "R54") (pin "1") (pinfunction "1_1") (pintype "passive"))
      (node (ref "R55") (pin "1") (pinfunction "1_1") (pintype "passive"))
      (node (ref "R59") (pin "2") (pinfunction "2_2") (pintype "passive"))
      (node (ref "U1") (pin "105") (pinfunction "VDDIO3_105") (pintype "power_in"))
      (node (ref "U1") (pin "11") (pinfunction "VDDIO1_11") (pintype "power_in"))
      (node (ref "U1") (pin "125") (pinfunction "VDDIO4_125") (pintype "power_in"))
      (node (ref "U1") (pin "52") (pinfunction "VDDBU_52") (pintype "power_in"))
      (node (ref "U1") (pin "57") (pinfunction "VDDIN_57") (pintype "power_in"))
      (node (ref "U1") (pin "62") (pinfunction "VDDIO2_62") (pintype "power_in"))
      (node (ref "U2") (pin "2") (pinfunction "OUT_2") (pintype "passive"))
      (node (ref "U3") (pin "1") (pinfunction "VDD1_1") (pintype "power_in"))
      (node (ref "U4") (pin "1") (pinfunction "VDD1_1") (pintype "power_in"))
      (node (ref "U5") (pin "1") (pinfunction "VDD1_1") (pintype "power_in"))
      (node (ref "U6") (pin "1") (pinfunction "VDD1_1") (pintype "power_in"))
      (node (ref "U7") (pin "PIN8") (pinfunction "VCC_PIN8") (pintype "bidirectional"))
      (node (ref "U8") (pin "+VOUT") (pinfunction "+VOUT_+VOUT") (pintype "bidirectional"))
    )
    (net (code "2") (name "+5V") (class "Default")
      (node (ref "AMPSEAL1") (pin "24") (pinfunction "24_24") (pintype "passive"))
      (node (ref "AMPSEAL1") (pin "25") (pinfunction "25_25") (pintype "passive"))
      (node (ref "AMPSEAL1") (pin "26") (pinfunction "26_26") (pintype "passive"))
      (node (ref "AMPSEAL1") (pin "27") (pinfunction "27_27") (pintype "passive"))
      (node (ref "AMPSEAL1") (pin "28") (pinfunction "28_28") (pintype "passive"))
      (node (ref "C48") (pin "1") (pinfunction "1_1") (pintype "passive"))
      (node (ref "C50") (pin "1") (pinfunction "1_1") (pintype "passive"))
      (node (ref "C59") (pin "1") (pinfunction "1_1") (pintype "passive"))
      (node (ref "C64") (pin "1") (pinfunction "1_1") (pintype "passive"))
      (node (ref "C68") (pin "1") (pinfunction "1_1") (pintype "passive"))
      (node (ref "C71") (pin "1") (pinfunction "1_1") (pintype "passive"))
      (node (ref "C80") (pin "1") (pinfunction "1_1") (pintype "passive"))
      (node (ref "IC10") (pin "9") (pinfunction "VCC2_9") (pintype "input"))
      (node (ref "IC11") (pin "3") (pinfunction "VO_3") (pintype "passive"))
      (node (ref "IC3") (pin "1") (pinfunction "VDD1_1") (pintype "bidirectional"))
      (node (ref "IC4") (pin "1") (pinfunction "VDD1_1") (pintype "bidirectional"))
      (node (ref "IC7") (pin "1") (pinfunction "VDD1_1") (pintype "bidirectional"))
      (node (ref "IC8") (pin "1") (pinfunction "VDD1_1") (pintype "bidirectional"))
      (node (ref "IC9") (pin "9") (pinfunction "VCC2_9") (pintype "input"))
      (node (ref "R58") (pin "2") (pinfunction "2_2") (pintype "passive"))
    )
    (net (code "3") (name "+12V") (class "Default")
      (node (ref "AMPSEAL1") (pin "2") (pinfunction "2_2") (pintype "passive"))
      (node (ref "C32") (pin "1") (pinfunction "1_1") (pintype "passive"))
      (node (ref "C33") (pin "1") (pinfunction "1_1") (pintype "passive"))
      (node (ref "C35") (pin "1") (pinfunction "1_1") (pintype "passive"))
      (node (ref "C36") (pin "1") (pinfunction "1_1") (pintype "passive"))
      (node (ref "C38") (pin "1") (pinfunction "1_1") (pintype "passive"))
      (node (ref "C39") (pin "1") (pinfunction "1_1") (pintype "passive"))
      (node (ref "C41") (pin "1") (pinfunction "1_1") (pintype "passive"))
      (node (ref "C42") (pin "1") (pinfunction "1_1") (pintype "passive"))
      (node (ref "C74") (pin "+") (pinfunction "+_+") (pintype "passive"))
      (node (ref "C75") (pin "1") (pinfunction "1_1") (pintype "passive"))
      (node (ref "C76") (pin "1") (pinfunction "1_1") (pintype "passive"))
      (node (ref "C79") (pin "1") (pinfunction "1_1") (pintype "passive"))
      (node (ref "IC11") (pin "1") (pinfunction "VI_1") (pintype "input"))
      (node (ref "PTC") (pin "P$1") (pinfunction "1_P$1") (pintype "passive"))
      (node (ref "R57") (pin "2") (pinfunction "2_2") (pintype "passive"))
      (node (ref "U3") (pin "8") (pinfunction "VDD2_8") (pintype "power_in"))
      (node (ref "U4") (pin "8") (pinfunction "VDD2_8") (pintype "power_in"))
      (node (ref "U5") (pin "8") (pinfunction "VDD2_8") (pintype "power_in"))
      (node (ref "U6") (pin "8") (pinfunction "VDD2_8") (pintype "power_in"))
      (node (ref "U8") (pin "+VIN1") (pinfunction "+VIN1_+VIN1") (pintype "bidirectional"))
      (node (ref "U8") (pin "+VIN2") (pinfunction "+VIN2_+VIN2") (pintype "bidirectional"))
    )
    (net (code "4") (name "/A0") (class "Default")
      (node (ref "C55") (pin "1") (pinfunction "1_1") (pintype "passive"))
      (node (ref "IC5") (pin "6") (pinfunction "OUT_6") (pintype "output"))
      (node (ref "R26") (pin "2") (pinfunction "2_2") (pintype "passive"))
      (node (ref "U1") (pin "78") (pinfunction "PA16_78") (pintype "bidirectional"))
    )
    (net (code "5") (name "/A1") (class "Default")
      (node (ref "C44") (pin "1") (pinfunction "1_1") (pintype "passive"))
      (node (ref "IC2") (pin "6") (pinfunction "OUT_6") (pintype "output"))
      (node (ref "R15") (pin "2") (pinfunction "2_2") (pintype "passive"))
      (node (ref "U1") (pin "79") (pinfunction "PA24_79") (pintype "bidirectional"))
    )
    (net (code "6") (name "/A2") (class "Default")
      (node (ref "C56") (pin "1") (pinfunction "1_1") (pintype "passive"))
      (node (ref "IC6") (pin "6") (pinfunction "OUT_6") (pintype "output"))
      (node (ref "R27") (pin "2") (pinfunction "2_2") (pintype "passive"))
      (node (ref "U1") (pin "80") (pinfunction "PA23_80") (pintype "bidirectional"))
    )
    (net (code "7") (name "/A3") (class "Default")
      (node (ref "C43") (pin "1") (pinfunction "1_1") (pintype "passive"))
      (node (ref "IC1") (pin "6") (pinfunction "OUT_6") (pintype "output"))
      (node (ref "R14") (pin "2") (pinfunction "2_2") (pintype "passive"))
      (node (ref "U1") (pin "81") (pinfunction "PA22_81") (pintype "bidirectional"))
    )
    (net (code "8") (name "/AIN0") (class "Default")
      (node (ref "AMPSEAL1") (pin "20") (pinfunction "20_20") (pintype "passive"))
      (node (ref "R16") (pin "2") (pinfunction "2_2") (pintype "passive"))
    )
    (net (code "9") (name "/AIN1") (class "Default")
      (node (ref "AMPSEAL1") (pin "21") (pinfunction "21_21") (pintype "passive"))
      (node (ref "R30") (pin "2") (pinfunction "2_2") (pintype "passive"))
    )
    (net (code "10") (name "/AIN2") (class "Default")
      (node (ref "AMPSEAL1") (pin "22") (pinfunction "22_22") (pintype "passive"))
      (node (ref "R18") (pin "2") (pinfunction "2_2") (pintype "passive"))
    )
    (net (code "11") (name "/AIN3") (class "Default")
      (node (ref "AMPSEAL1") (pin "23") (pinfunction "23_23") (pintype "passive"))
      (node (ref "R28") (pin "2") (pinfunction "2_2") (pintype "passive"))
    )
    (net (code "12") (name "/AVREF") (class "Default")
      (node (ref "C20") (pin "1") (pinfunction "1_1") (pintype "passive"))
      (node (ref "L3") (pin "2") (pinfunction "2_2") (pintype "passive"))
      (node (ref "U1") (pin "75") (pinfunction "ADVREF_75") (pintype "power_in"))
    )
    (net (code "13") (name "/CANH0") (class "Default")
      (node (ref "AMPSEAL1") (pin "9") (pinfunction "9_9") (pintype "passive"))
      (node (ref "IC9") (pin "12") (pinfunction "CANH_12") (pintype "input"))
      (node (ref "SJ1") (pin "1") (pinfunction "1_1") (pintype "passive"))
    )
    (net (code "14") (name "/CANH1") (class "Default")
      (node (ref "AMPSEAL1") (pin "11") (pinfunction "11_11") (pintype "passive"))
      (node (ref "IC10") (pin "12") (pinfunction "CANH_12") (pintype "input"))
      (node (ref "SJ3") (pin "1") (pinfunction "1_1") (pintype "passive"))
    )
    (net (code "15") (name "/CANL0") (class "Default")
      (node (ref "AMPSEAL1") (pin "10") (pinfunction "10_10") (pintype "passive"))
      (node (ref "IC9") (pin "13") (pinfunction "CANL_13") (pintype "input"))
      (node (ref "SJ2") (pin "1") (pinfunction "1_1") (pintype "passive"))
    )
    (net (code "16") (name "/CANL1") (class "Default")
      (node (ref "AMPSEAL1") (pin "12") (pinfunction "12_12") (pintype "passive"))
      (node (ref "IC10") (pin "13") (pinfunction "CANL_13") (pintype "input"))
      (node (ref "SJ4") (pin "1") (pinfunction "1_1") (pintype "passive"))
    )
    (net (code "17") (name "/CANRX0") (class "Default")
      (node (ref "IC9") (pin "3") (pinfunction "RXD_3") (pintype "input"))
      (node (ref "U1") (pin "24") (pinfunction "PA1_24") (pintype "bidirectional"))
    )
    (net (code "18") (name "/CANRX1") (class "Default")
      (node (ref "IC10") (pin "3") (pinfunction "RXD_3") (pintype "input"))
      (node (ref "U1") (pin "76") (pinfunction "PB15_76") (pintype "bidirectional"))
    )
    (net (code "19") (name "/CANTX0") (class "Default")
      (node (ref "IC9") (pin "6") (pinfunction "TXD_6") (pintype "input"))
      (node (ref "U1") (pin "23") (pinfunction "PA0_23") (pintype "bidirectional"))
    )
    (net (code "20") (name "/CANTX1") (class "Default")
      (node (ref "IC10") (pin "6") (pinfunction "TXD_6") (pintype "input"))
      (node (ref "U1") (pin "140") (pinfunction "PB14_140") (pintype "bidirectional"))
    )
    (net (code "21") (name "/D+") (class "Default")
      (node (ref "R3") (pin "1") (pinfunction "1_1") (pintype "passive"))
      (node (ref "U1") (pin "37") (pinfunction "DHSDP_37") (pintype "bidirectional"))
      (node (ref "X1") (pin "3") (pinfunction "3_3") (pintype "passive"))
      (node (ref "Z1") (pin "1") (pinfunction "1_1") (pintype "passive"))
    )
    (net (code "22") (name "/D-") (class "Default")
      (node (ref "R2") (pin "1") (pinfunction "1_1") (pintype "passive"))
      (node (ref "U1") (pin "38") (pinfunction "DHSDM_38") (pintype "bidirectional"))
      (node (ref "X1") (pin "2") (pinfunction "2_2") (pintype "passive"))
      (node (ref "Z2") (pin "1") (pinfunction "1_1") (pintype "passive"))
    )
    (net (code "23") (name "/D2") (class "Default")
      (node (ref "U1") (pin "144") (pinfunction "PB25_144") (pintype "bidirectional"))
      (node (ref "U4") (pin "3") (pinfunction "VIB_3") (pintype "input"))
    )
    (net (code "24") (name "/D3") (class "Default")
      (node (ref "U1") (pin "139") (pinfunction "PC28_139") (pintype "bidirectional"))
      (node (ref "U4") (pin "2") (pinfunction "VIA_2") (pintype "input"))
    )
    (net (code "25") (name "/D4") (class "Default")
      (node (ref "U1") (pin "137") (pinfunction "PC26_137") (pintype "bidirectional"))
      (node (ref "U6") (pin "3") (pinfunction "VIB_3") (pintype "input"))
    )
    (net (code "26") (name "/D5") (class "Default")
      (node (ref "U1") (pin "136") (pinfunction "PC25_136") (pintype "bidirectional"))
      (node (ref "U6") (pin "2") (pinfunction "VIA_2") (pintype "input"))
    )
    (net (code "27") (name "/D6") (class "Default")
      (node (ref "U1") (pin "135") (pinfunction "PC24_135") (pintype "bidirectional"))
      (node (ref "U5") (pin "3") (pinfunction "VIB_3") (pintype "input"))
    )
    (net (code "28") (name "/D7") (class "Default")
      (node (ref "U1") (pin "134") (pinfunction "PC23_134") (pintype "bidirectional"))
      (node (ref "U5") (pin "2") (pinfunction "VIA_2") (pintype "input"))
    )
    (net (code "29") (name "/D8") (class "Default")
      (node (ref "U1") (pin "133") (pinfunction "PC22_133") (pintype "bidirectional"))
      (node (ref "U3") (pin "3") (pinfunction "VIB_3") (pintype "input"))
    )
    (net (code "30") (name "/D9") (class "Default")
      (node (ref "U1") (pin "132") (pinfunction "PC21_132") (pintype "bidirectional"))
      (node (ref "U3") (pin "2") (pinfunction "VIA_2") (pintype "input"))
    )
    (net (code "31") (name "/D13") (class "Default")
      (node (ref "R5") (pin "2") (pinfunction "2_2") (pintype "passive"))
      (node (ref "U1") (pin "68") (pinfunction "PB27_68") (pintype "bidirectional"))
    )
    (net (code "32") (name "/D18") (class "Default")
      (node (ref "IWIFI") (pin "10") (pinfunction "10_10") (pintype "passive"))
      (node (ref "U1") (pin "4") (pinfunction "PA11_4") (pintype "bidirectional"))
    )
    (net (code "33") (name "/D42") (class "Default")
      (node (ref "IWIFI") (pin "11") (pinfunction "11_11") (pintype "passive"))
      (node (ref "U1") (pin "71") (pinfunction "PA19_71") (pintype "bidirectional"))
    )
    (net (code "34") (name "/D48") (class "Default")
      (node (ref "R42") (pin "1") (pinfunction "1_1") (pintype "passive"))
      (node (ref "R45") (pin "2") (pinfunction "2_2") (pintype "passive"))
      (node (ref "U1") (pin "97") (pinfunction "PC15_97") (pintype "bidirectional"))
    )
    (net (code "35") (name "/D49") (class "Default")
      (node (ref "R43") (pin "1") (pinfunction "1_1") (pintype "passive"))
      (node (ref "R47") (pin "2") (pinfunction "2_2") (pintype "passive"))
      (node (ref "U1") (pin "96") (pinfunction "PC14_96") (pintype "bidirectional"))
    )
    (net (code "36") (name "/D50") (class "Default")
      (node (ref "R48") (pin "1") (pinfunction "1_1") (pintype "passive"))
      (node (ref "R51") (pin "2") (pinfunction "2_2") (pintype "passive"))
      (node (ref "U1") (pin "95") (pinfunction "PC13_95") (pintype "bidirectional"))
    )
    (net (code "37") (name "/D51") (class "Default")
      (node (ref "R49") (pin "1") (pinfunction "1_1") (pintype "passive"))
      (node (ref "R53") (pin "2") (pinfunction "2_2") (pintype "passive"))
      (node (ref "U1") (pin "94") (pinfunction "PC12_94") (pintype "bidirectional"))
    )
    (net (code "38") (name "/DIN0") (class "Default")
      (node (ref "AMPSEAL1") (pin "32") (pinfunction "32_32") (pintype "passive"))
      (node (ref "R44") (pin "1") (pinfunction "1_1") (pintype "passive"))
    )
    (net (code "39") (name "/DIN1") (class "Default")
      (node (ref "AMPSEAL1") (pin "33") (pinfunction "33_33") (pintype "passive"))
      (node (ref "R46") (pin "1") (pinfunction "1_1") (pintype "passive"))
    )
    (net (code "40") (name "/DIN2") (class "Default")
      (node (ref "AMPSEAL1") (pin "34") (pinfunction "34_34") (pintype "passive"))
      (node (ref "R50") (pin "1") (pinfunction "1_1") (pintype "passive"))
    )
    (net (code "41") (name "/DIN3") (class "Default")
      (node (ref "AMPSEAL1") (pin "35") (pinfunction "35_35") (pintype "passive"))
      (node (ref "R52") (pin "1") (pinfunction "1_1") (pintype "passive"))
    )
    (net (code "42") (name "/DOUT0") (class "Default")
      (node (ref "AMPSEAL1") (pin "3") (pinfunction "3_3") (pintype "passive"))
      (node (ref "D7") (pin "C") (pinfunction "C_C") (pintype "passive"))
      (node (ref "T7") (pin "2") (pinfunction "D_2") (pintype "passive"))
      (node (ref "T7") (pin "4") (pinfunction "D_4") (pintype "passive"))
    )
    (net (code "43") (name "/DOUT1") (class "Default")
      (node (ref "AMPSEAL1") (pin "4") (pinfunction "4_4") (pintype "passive"))
      (node (ref "D8") (pin "C") (pinfunction "C_C") (pintype "passive"))
      (node (ref "T8") (pin "2") (pinfunction "D_2") (pintype "passive"))
      (node (ref "T8") (pin "4") (pinfunction "D_4") (pintype "passive"))
    )
    (net (code "44") (name "/DOUT2") (class "Default")
      (node (ref "AMPSEAL1") (pin "5") (pinfunction "5_5") (pintype "passive"))
      (node (ref "D5") (pin "C") (pinfunction "C_C") (pintype "passive"))
      (node (ref "T5") (pin "2") (pinfunction "D_2") (pintype "passive"))
      (node (ref "T5") (pin "4") (pinfunction "D_4") (pintype "passive"))
    )
    (net (code "45") (name "/DOUT3") (class "Default")
      (node (ref "AMPSEAL1") (pin "6") (pinfunction "6_6") (pintype "passive"))
      (node (ref "D6") (pin "C") (pinfunction "C_C") (pintype "passive"))
      (node (ref "T6") (pin "2") (pinfunction "D_2") (pintype "passive"))
      (node (ref "T6") (pin "4") (pinfunction "D_4") (pintype "passive"))
    )
    (net (code "46") (name "/DOUT4") (class "Default")
      (node (ref "AMPSEAL1") (pin "15") (pinfunction "15_15") (pintype "passive"))
      (node (ref "D3") (pin "C") (pinfunction "C_C") (pintype "passive"))
      (node (ref "T3") (pin "2") (pinfunction "D_2") (pintype "passive"))
      (node (ref "T3") (pin "4") (pinfunction "D_4") (pintype "passive"))
    )
    (net (code "47") (name "/DOUT5") (class "Default")
      (node (ref "AMPSEAL1") (pin "16") (pinfunction "16_16") (pintype "passive"))
      (node (ref "D4") (pin "C") (pinfunction "C_C") (pintype "passive"))
      (node (ref "T4") (pin "2") (pinfunction "D_2") (pintype "passive"))
      (node (ref "T4") (pin "4") (pinfunction "D_4") (pintype "passive"))
    )
    (net (code "48") (name "/DOUT6") (class "Default")
      (node (ref "AMPSEAL1") (pin "17") (pinfunction "17_17") (pintype "passive"))
      (node (ref "D1") (pin "C") (pinfunction "C_C") (pintype "passive"))
      (node (ref "T1") (pin "2") (pinfunction "D_2") (pintype "passive"))
      (node (ref "T1") (pin "4") (pinfunction "D_4") (pintype "passive"))
    )
    (net (code "49") (name "/DOUT7") (class "Default")
      (node (ref "AMPSEAL1") (pin "18") (pinfunction "18_18") (pintype "passive"))
      (node (ref "D2") (pin "C") (pinfunction "C_C") (pintype "passive"))
      (node (ref "T2") (pin "2") (pinfunction "D_2") (pintype "passive"))
      (node (ref "T2") (pin "4") (pinfunction "D_4") (pintype "passive"))
    )
    (net (code "50") (name "/MASTER-RESET") (class "Default")
      (node (ref "C28") (pin "2") (pinfunction "2_2") (pintype "passive"))
      (node (ref "RESET") (pin "P$2") (pinfunction "P$5_P$2") (pintype "bidirectional"))
      (node (ref "U1") (pin "47") (pinfunction "NRSTB_47") (pintype "input"))
    )
    (net (code "51") (name "/MDRIVE0") (class "Default")
      (node (ref "R12") (pin "1") (pinfunction "1_1") (pintype "passive"))
      (node (ref "T7") (pin "1") (pinfunction "G_1") (pintype "passive"))
      (node (ref "U6") (pin "6") (pinfunction "VOB_6") (pintype "output"))
    )
    (net (code "52") (name "/MDRIVE1") (class "Default")
      (node (ref "R13") (pin "1") (pinfunction "1_1") (pintype "passive"))
      (node (ref "T8") (pin "1") (pinfunction "G_1") (pintype "passive"))
      (node (ref "U6") (pin "7") (pinfunction "VOA_7") (pintype "output"))
    )
    (net (code "53") (name "/MDRIVE2") (class "Default")
      (node (ref "R10") (pin "1") (pinfunction "1_1") (pintype "passive"))
      (node (ref "T5") (pin "1") (pinfunction "G_1") (pintype "passive"))
      (node (ref "U5") (pin "6") (pinfunction "VOB_6") (pintype "output"))
    )
    (net (code "54") (name "/MDRIVE3") (class "Default")
      (node (ref "R11") (pin "1") (pinfunction "1_1") (pintype "passive"))
      (node (ref "T6") (pin "1") (pinfunction "G_1") (pintype "passive"))
      (node (ref "U5") (pin "7") (pinfunction "VOA_7") (pintype "output"))
    )
    (net (code "55") (name "/MDRIVE4") (class "Default")
      (node (ref "R8") (pin "1") (pinfunction "1_1") (pintype "passive"))
      (node (ref "T3") (pin "1") (pinfunction "G_1") (pintype "passive"))
      (node (ref "U4") (pin "6") (pinfunction "VOB_6") (pintype "output"))
    )
    (net (code "56") (name "/MDRIVE5") (class "Default")
      (node (ref "R9") (pin "1") (pinfunction "1_1") (pintype "passive"))
      (node (ref "T4") (pin "1") (pinfunction "G_1") (pintype "passive"))
      (node (ref "U4") (pin "7") (pinfunction "VOA_7") (pintype "output"))
    )
    (net (code "57") (name "/MDRIVE6") (class "Default")
      (node (ref "R6") (pin "1") (pinfunction "1_1") (pintype "passive"))
      (node (ref "T1") (pin "1") (pinfunction "G_1") (pintype "passive"))
      (node (ref "U3") (pin "6") (pinfunction "VOB_6") (pintype "output"))
    )
    (net (code "58") (name "/MDRIVE7") (class "Default")
      (node (ref "R7") (pin "1") (pinfunction "1_1") (pintype "passive"))
      (node (ref "T2") (pin "1") (pinfunction "G_1") (pintype "passive"))
      (node (ref "U3") (pin "7") (pinfunction "VOA_7") (pintype "output"))
    )
    (net (code "59") (name "/RX2") (class "Default")
      (node (ref "IWIFI") (pin "4") (pinfunction "4_4") (pintype "passive"))
      (node (ref "U1") (pin "5") (pinfunction "PA12_5") (pintype "bidirectional"))
    )
    (net (code "60") (name "/SCL") (class "Default")
      (node (ref "R54") (pin "2") (pinfunction "2_2") (pintype "passive"))
      (node (ref "U1") (pin "87") (pinfunction "PB13_87") (pintype "bidirectional"))
      (node (ref "U7") (pin "PIN6") (pinfunction "SCL_PIN6") (pintype "bidirectional"))
    )
    (net (code "61") (name "/SDA") (class "Default")
      (node (ref "R55") (pin "2") (pinfunction "2_2") (pintype "passive"))
      (node (ref "U1") (pin "86") (pinfunction "PB12_86") (pintype "bidirectional"))
      (node (ref "U7") (pin "PIN5") (pinfunction "SDA_PIN5") (pintype "bidirectional"))
    )
    (net (code "62") (name "/TX2") (class "Default")
      (node (ref "IWIFI") (pin "3") (pinfunction "3_3") (pintype "passive"))
      (node (ref "U1") (pin "6") (pinfunction "PA13_6") (pintype "bidirectional"))
    )
    (net (code "63") (name "/VBG") (class "Default")
      (node (ref "C27") (pin "1") (pinfunction "1_1") (pintype "passive"))
      (node (ref "R4") (pin "2") (pinfunction "2_2") (pintype "passive"))
      (node (ref "U1") (pin "40") (pinfunction "VBG_40") (pintype "passive"))
    )
    (net (code "64") (name "/VBUS") (class "Default")
      (node (ref "C29") (pin "1") (pinfunction "1_1") (pintype "passive"))
      (node (ref "U1") (pin "39") (pinfunction "VBUS_39") (pintype "power_in"))
      (node (ref "U2") (pin "3") (pinfunction "IN_3") (pintype "input"))
      (node (ref "X1") (pin "1") (pinfunction "1_1") (pintype "passive"))
    )
    (net (code "65") (name "/VDDANA") (class "Default")
      (node (ref "C10") (pin "1") (pinfunction "1_1") (pintype "passive"))
      (node (ref "C11") (pin "1") (pinfunction "1_1") (pintype "passive"))
      (node (ref "L1") (pin "2") (pinfunction "2_2") (pintype "passive"))
      (node (ref "U1") (pin "73") (pinfunction "VDDANA_73") (pintype "power_in"))
    )
    (net (code "66") (name "/VDDOUT") (class "Default")
      (node (ref "C12") (pin "1") (pinfunction "1_1") (pintype "passive"))
      (node (ref "C13") (pin "1") (pinfunction "1_1") (pintype "passive"))
      (node (ref "C14") (pin "1") (pinfunction "1_1") (pintype "passive"))
      (node (ref "C15") (pin "1") (pinfunction "1_1") (pintype "passive"))
      (node (ref "C16") (pin "1") (pinfunction "1_1") (pintype "passive"))
      (node (ref "C17") (pin "1") (pinfunction "1_1") (pintype "passive"))
      (node (ref "C18") (pin "1") (pinfunction "1_1") (pintype "passive"))
      (node (ref "L4") (pin "1") (pinfunction "1_1") (pintype "passive"))
      (node (ref "U1") (pin "10") (pinfunction "VDDCORE1_10") (pintype "input"))
      (node (ref "U1") (pin "104") (pinfunction "VDDCORE4_104") (pintype "input"))
      (node (ref "U1") (pin "124") (pinfunction "VDDCORE5_124") (pintype "input"))
      (node (ref "U1") (pin "45") (pinfunction "VDDCORE2_45") (pintype "input"))
      (node (ref "U1") (pin "56") (pinfunction "VDDOUT_56") (pintype "output"))
      (node (ref "U1") (pin "61") (pinfunction "VDDCORE3_61") (pintype "input"))
    )
    (net (code "67") (name "/VDDOUTMI") (class "Default")
      (node (ref "C8") (pin "1") (pinfunction "1_1") (pintype "passive"))
      (node (ref "C9") (pin "1") (pinfunction "1_1") (pintype "passive"))
      (node (ref "L2") (pin "2") (pinfunction "2_2") (pintype "passive"))
      (node (ref "U1") (pin "41") (pinfunction "VDDUTMI_41") (pintype "input"))
    )
    (net (code "68") (name "/VDDPLL") (class "Default")
      (node (ref "C21") (pin "1") (pinfunction "1_1") (pintype "passive"))
      (node (ref "C22") (pin "1") (pinfunction "1_1") (pintype "passive"))
      (node (ref "L4") (pin "2") (pinfunction "2_2") (pintype "passive"))
      (node (ref "U1") (pin "34") (pinfunction "VDDPLL_34") (pintype "input"))
    )
    (net (code "69") (name "/VIN(+12V)") (class "Default")
      (node (ref "AMPSEAL1") (pin "1") (pinfunction "1_1") (pintype "passive"))
      (node (ref "D9") (pin "A") (pinfunction "A_A") (pintype "passive"))
    )
    (net (code "70") (name "/XIN") (class "Default")
      (node (ref "C24") (pin "1") (pinfunction "1_1") (pintype "passive"))
      (node (ref "U1") (pin "36") (pinfunction "XIN_36") (pintype "input"))
      (node (ref "Y1") (pin "1") (pinfunction "C1_1") (pintype "passive"))
    )
    (net (code "71") (name "/XIN32") (class "Default")
      (node (ref "C26") (pin "1") (pinfunction "1_1") (pintype "passive"))
      (node (ref "U1") (pin "48") (pinfunction "XIN32_48") (pintype "output"))
      (node (ref "Y2") (pin "P$2") (pinfunction "2_P$2") (pintype "bidirectional"))
    )
    (net (code "72") (name "/XOUT") (class "Default")
      (node (ref "C23") (pin "1") (pinfunction "1_1") (pintype "passive"))
      (node (ref "U1") (pin "35") (pinfunction "XOUT_35") (pintype "output"))
      (node (ref "Y1") (pin "3") (pinfunction "C2_3") (pintype "passive"))
    )
    (net (code "73") (name "/XOUT32") (class "Default")
      (node (ref "C25") (pin "1") (pinfunction "1_1") (pintype "passive"))
      (node (ref "U1") (pin "49") (pinfunction "XOUT32_49") (pintype "output"))
      (node (ref "Y2") (pin "P$1") (pinfunction "1_P$1") (pintype "bidirectional"))
    )
    (net (code "74") (name "GND") (class "Default")
      (node (ref "+12V") (pin "C") (pinfunction "C_C") (pintype "passive"))
      (node (ref "+5V") (pin "C") (pinfunction "C_C") (pintype "passive"))
      (node (ref "AMPSEAL1") (pin "13") (pinfunction "13_13") (pintype "passive"))
      (node (ref "AMPSEAL1") (pin "14") (pinfunction "14_14") (pintype "passive"))
      (node (ref "AMPSEAL1") (pin "19") (pinfunction "19_19") (pintype "passive"))
      (node (ref "AMPSEAL1") (pin "29") (pinfunction "29_29") (pintype "passive"))
      (node (ref "AMPSEAL1") (pin "30") (pinfunction "30_30") (pintype "passive"))
      (node (ref "AMPSEAL1") (pin "31") (pinfunction "31_31") (pintype "passive"))
      (node (ref "AMPSEAL1") (pin "7") (pinfunction "7_7") (pintype "passive"))
      (node (ref "AMPSEAL1") (pin "8") (pinfunction "8_8") (pintype "passive"))
      (node (ref "C32") (pin "2") (pinfunction "2_2") (pintype "passive"))
      (node (ref "C33") (pin "2") (pinfunction "2_2") (pintype "passive"))
      (node (ref "C35") (pin "2") (pinfunction "2_2") (pintype "passive"))
      (node (ref "C36") (pin "2") (pinfunction "2_2") (pintype "passive"))
      (node (ref "C38") (pin "2") (pinfunction "2_2") (pintype "passive"))
      (node (ref "C39") (pin "2") (pinfunction "2_2") (pintype "passive"))
      (node (ref "C41") (pin "2") (pinfunction "2_2") (pintype "passive"))
      (node (ref "C42") (pin "2") (pinfunction "2_2") (pintype "passive"))
      (node (ref "C47") (pin "2") (pinfunction "2_2") (pintype "passive"))
      (node (ref "C48") (pin "2") (pinfunction "2_2") (pintype "passive"))
      (node (ref "C49") (pin "2") (pinfunction "2_2") (pintype "passive"))
      (node (ref "C50") (pin "2") (pinfunction "2_2") (pintype "passive"))
      (node (ref "C58") (pin "2") (pinfunction "2_2") (pintype "passive"))
      (node (ref "C59") (pin "2") (pinfunction "2_2") (pintype "passive"))
      (node (ref "C63") (pin "2") (pinfunction "2_2") (pintype "passive"))
      (node (ref "C64") (pin "2") (pinfunction "2_2") (pintype "passive"))
      (node (ref "C68") (pin "2") (pinfunction "2_2") (pintype "passive"))
      (node (ref "C69") (pin "2") (pinfunction "2_2") (pintype "passive"))
      (node (ref "C71") (pin "2") (pinfunction "2_2") (pintype "passive"))
      (node (ref "C72") (pin "2") (pinfunction "2_2") (pintype "passive"))
      (node (ref "C74") (pin "-") (pinfunction "-_-") (pintype "passive"))
      (node (ref "C75") (pin "2") (pinfunction "2_2") (pintype "passive"))
      (node (ref "C76") (pin "2") (pinfunction "2_2") (pintype "passive"))
      (node (ref "C78") (pin "1") (pinfunction "1_1") (pintype "passive"))
      (node (ref "C79") (pin "2") (pinfunction "2_2") (pintype "passive"))
      (node (ref "C80") (pin "2") (pinfunction "2_2") (pintype "passive"))
      (node (ref "D1") (pin "A") (pinfunction "A_A") (pintype "passive"))
      (node (ref "D2") (pin "A") (pinfunction "A_A") (pintype "passive"))
      (node (ref "D3") (pin "A") (pinfunction "A_A") (pintype "passive"))
      (node (ref "D4") (pin "A") (pinfunction "A_A") (pintype "passive"))
      (node (ref "D5") (pin "A") (pinfunction "A_A") (pintype "passive"))
      (node (ref "D6") (pin "A") (pinfunction "A_A") (pintype "passive"))
      (node (ref "D7") (pin "A") (pinfunction "A_A") (pintype "passive"))
      (node (ref "D8") (pin "A") (pinfunction "A_A") (pintype "passive"))
      (node (ref "IC10") (pin "10") (pinfunction "GND2_10") (pintype "input"))
      (node (ref "IC10") (pin "15") (pinfunction "GND2_15") (pintype "input"))
      (node (ref "IC10") (pin "16") (pinfunction "GND2_16") (pintype "input"))
      (node (ref "IC11") (pin "4") (pinfunction "GND_4") (pintype "passive"))
      (node (ref "IC3") (pin "3") (pinfunction "SHDN_3") (pintype "bidirectional"))
      (node (ref "IC3") (pin "4") (pinfunction "GND1_4") (pintype "bidirectional"))
      (node (ref "IC4") (pin "3") (pinfunction "SHDN_3") (pintype "bidirectional"))
      (node (ref "IC4") (pin "4") (pinfunction "GND1_4") (pintype "bidirectional"))
      (node (ref "IC7") (pin "3") (pinfunction "SHDN_3") (pintype "bidirectional"))
      (node (ref "IC7") (pin "4") (pinfunction "GND1_4") (pintype "bidirectional"))
      (node (ref "IC8") (pin "3") (pinfunction "SHDN_3") (pintype "bidirectional"))
      (node (ref "IC8") (pin "4") (pinfunction "GND1_4") (pintype "bidirectional"))
      (node (ref "IC9") (pin "10") (pinfunction "GND2_10") (pintype "input"))
      (node (ref "IC9") (pin "15") (pinfunction "GND2_15") (pintype "input"))
      (node (ref "IC9") (pin "16") (pinfunction "GND2_16") (pintype "input"))
      (node (ref "OK1") (pin "2") (pinfunction "C_2") (pintype "passive"))
      (node (ref "OK1") (pin "4") (pinfunction "C_4") (pintype "passive"))
      (node (ref "OK2") (pin "2") (pinfunction "C_2") (pintype "passive"))
      (node (ref "OK2") (pin "4") (pinfunction "C_4") (pintype "passive"))
      (node (ref "R10") (pin "2") (pinfunction "2_2") (pintype "passive"))
      (node (ref "R11") (pin "2") (pinfunction "2_2") (pintype "passive"))
      (node (ref "R12") (pin "2") (pinfunction "2_2") (pintype "passive"))
      (node (ref "R13") (pin "2") (pinfunction "2_2") (pintype "passive"))
      (node (ref "R20") (pin "1") (pinfunction "1_1") (pintype "passive"))
      (node (ref "R22") (pin "1") (pinfunction "1_1") (pintype "passive"))
      (node (ref "R32") (pin "1") (pinfunction "1_1") (pintype "passive"))
      (node (ref "R34") (pin "1") (pinfunction "1_1") (pintype "passive"))
      (node (ref "R6") (pin "2") (pinfunction "2_2") (pintype "passive"))
      (node (ref "R7") (pin "2") (pinfunction "2_2") (pintype "passive"))
      (node (ref "R8") (pin "2") (pinfunction "2_2") (pintype "passive"))
      (node (ref "R9") (pin "2") (pinfunction "2_2") (pintype "passive"))
      (node (ref "T1") (pin "3") (pinfunction "S_3") (pintype "passive"))
      (node (ref "T2") (pin "3") (pinfunction "S_3") (pintype "passive"))
      (node (ref "T3") (pin "3") (pinfunction "S_3") (pintype "passive"))
      (node (ref "T4") (pin "3") (pinfunction "S_3") (pintype "passive"))
      (node (ref "T5") (pin "3") (pinfunction "S_3") (pintype "passive"))
      (node (ref "T6") (pin "3") (pinfunction "S_3") (pintype "passive"))
      (node (ref "T7") (pin "3") (pinfunction "S_3") (pintype "passive"))
      (node (ref "T8") (pin "3") (pinfunction "S_3") (pintype "passive"))
      (node (ref "TVS") (pin "A") (pinfunction "A_A") (pintype "passive"))
      (node (ref "U3") (pin "5") (pinfunction "GND2_5") (pintype "passive"))
      (node (ref "U4") (pin "5") (pinfunction "GND2_5") (pintype "passive"))
      (node (ref "U5") (pin "5") (pinfunction "GND2_5") (pintype "passive"))
      (node (ref "U6") (pin "5") (pinfunction "GND2_5") (pintype "passive"))
      (node (ref "U8") (pin "-VIN1") (pinfunction "-VIN1_-VIN1") (pintype "bidirectional"))
      (node (ref "U8") (pin "-VIN2") (pinfunction "-VIN2_-VIN2") (pintype "bidirectional"))
      (node (ref "ZEN") (pin "A") (pinfunction "A_A") (pintype "passive"))
    )
    (net (code "75") (name "IGND") (class "Default")
      (node (ref "+3.3V") (pin "C") (pinfunction "C_C") (pintype "passive"))
      (node (ref "C1") (pin "2") (pinfunction "2_2") (pintype "passive"))
      (node (ref "C10") (pin "2") (pinfunction "2_2") (pintype "passive"))
      (node (ref "C11") (pin "2") (pinfunction "2_2") (pintype "passive"))
      (node (ref "C12") (pin "2") (pinfunction "2_2") (pintype "passive"))
      (node (ref "C13") (pin "2") (pinfunction "2_2") (pintype "passive"))
      (node (ref "C14") (pin "2") (pinfunction "2_2") (pintype "passive"))
      (node (ref "C15") (pin "2") (pinfunction "2_2") (pintype "passive"))
      (node (ref "C16") (pin "2") (pinfunction "2_2") (pintype "passive"))
      (node (ref "C17") (pin "2") (pinfunction "2_2") (pintype "passive"))
      (node (ref "C18") (pin "2") (pinfunction "2_2") (pintype "passive"))
      (node (ref "C19") (pin "2") (pinfunction "2_2") (pintype "passive"))
      (node (ref "C2") (pin "2") (pinfunction "2_2") (pintype "passive"))
      (node (ref "C20") (pin "2") (pinfunction "2_2") (pintype "passive"))
      (node (ref "C21") (pin "2") (pinfunction "2_2") (pintype "passive"))
      (node (ref "C22") (pin "2") (pinfunction "2_2") (pintype "passive"))
      (node (ref "C23") (pin "2") (pinfunction "2_2") (pintype "passive"))
      (node (ref "C24") (pin "2") (pinfunction "2_2") (pintype "passive"))
      (node (ref "C25") (pin "2") (pinfunction "2_2") (pintype "passive"))
      (node (ref "C26") (pin "2") (pinfunction "2_2") (pintype "passive"))
      (node (ref "C27") (pin "2") (pinfunction "2_2") (pintype "passive"))
      (node (ref "C29") (pin "2") (pinfunction "2_2") (pintype "passive"))
      (node (ref "C3") (pin "2") (pinfunction "2_2") (pintype "passive"))
      (node (ref "C30") (pin "2") (pinfunction "2_2") (pintype "passive"))
      (node (ref "C31") (pin "2") (pinfunction "2_2") (pintype "passive"))
      (node (ref "C34") (pin "2") (pinfunction "2_2") (pintype "passive"))
      (node (ref "C37") (pin "2") (pinfunction "2_2") (pintype "passive"))
      (node (ref "C4") (pin "2") (pinfunction "2_2") (pintype "passive"))
      (node (ref "C40") (pin "2") (pinfunction "2_2") (pintype "passive"))
      (node (ref "C45") (pin "2") (pinfunction "2_2") (pintype "passive"))
      (node (ref "C46") (pin "2") (pinfunction "2_2") (pintype "passive"))
      (node (ref "C5") (pin "2") (pinfunction "2_2") (pintype "passive"))
      (node (ref "C51") (pin "2") (pinfunction "2_2") (pintype "passive"))
      (node (ref "C52") (pin "2") (pinfunction "2_2") (pintype "passive"))
      (node (ref "C53") (pin "2") (pinfunction "2_2") (pintype "passive"))
      (node (ref "C54") (pin "2") (pinfunction "2_2") (pintype "passive"))
      (node (ref "C57") (pin "2") (pinfunction "2_2") (pintype "passive"))
      (node (ref "C6") (pin "2") (pinfunction "2_2") (pintype "passive"))
      (node (ref "C60") (pin "2") (pinfunction "2_2") (pintype "passive"))
      (node (ref "C61") (pin "2") (pinfunction "2_2") (pintype "passive"))
      (node (ref "C62") (pin "2") (pinfunction "2_2") (pintype "passive"))
      (node (ref "C65") (pin "2") (pinfunction "2_2") (pintype "passive"))
      (node (ref "C66") (pin "2") (pinfunction "2_2") (pintype "passive"))
      (node (ref "C67") (pin "2") (pinfunction "2_2") (pintype "passive"))
      (node (ref "C7") (pin "2") (pinfunction "2_2") (pintype "passive"))
      (node (ref "C70") (pin "2") (pinfunction "2_2") (pintype "passive"))
      (node (ref "C73") (pin "2") (pinfunction "2_2") (pintype "passive"))
      (node (ref "C77") (pin "2") (pinfunction "2_2") (pintype "passive"))
      (node (ref "C78") (pin "2") (pinfunction "2_2") (pintype "passive"))
      (node (ref "C8") (pin "2") (pinfunction "2_2") (pintype "passive"))
      (node (ref "C9") (pin "2") (pinfunction "2_2") (pintype "passive"))
      (node (ref "IC1") (pin "4") (pinfunction "V-_4") (pintype "power_in"))
      (node (ref "IC10") (pin "2") (pinfunction "GND1_2") (pintype "input"))
      (node (ref "IC10") (pin "7") (pinfunction "GND1_7") (pintype "input"))
      (node (ref "IC10") (pin "8") (pinfunction "GND1_8") (pintype "input"))
      (node (ref "IC2") (pin "4") (pinfunction "V-_4") (pintype "power_in"))
      (node (ref "IC3") (pin "5") (pinfunction "GND2_5") (pintype "bidirectional"))
      (node (ref "IC4") (pin "5") (pinfunction "GND2_5") (pintype "bidirectional"))
      (node (ref "IC5") (pin "4") (pinfunction "V-_4") (pintype "power_in"))
      (node (ref "IC6") (pin "4") (pinfunction "V-_4") (pintype "power_in"))
      (node (ref "IC7") (pin "5") (pinfunction "GND2_5") (pintype "bidirectional"))
      (node (ref "IC8") (pin "5") (pinfunction "GND2_5") (pintype "bidirectional"))
      (node (ref "IC9") (pin "2") (pinfunction "GND1_2") (pintype "input"))
      (node (ref "IC9") (pin "7") (pinfunction "GND1_7") (pintype "input"))
      (node (ref "IC9") (pin "8") (pinfunction "GND1_8") (pintype "input"))
      (node (ref "IWIFI") (pin "2") (pinfunction "2_2") (pintype "passive"))
      (node (ref "LED") (pin "C") (pinfunction "C_C") (pintype "passive"))
      (node (ref "OK1") (pin "5") (pinfunction "EMIT_5") (pintype "passive"))
      (node (ref "OK1") (pin "7") (pinfunction "EMIT_7") (pintype "passive"))
      (node (ref "OK2") (pin "5") (pinfunction "EMIT_5") (pintype "passive"))
      (node (ref "OK2") (pin "7") (pinfunction "EMIT_7") (pintype "passive"))
      (node (ref "R24") (pin "2") (pinfunction "2_2") (pintype "passive"))
      (node (ref "R25") (pin "2") (pinfunction "2_2") (pintype "passive"))
      (node (ref "R36") (pin "2") (pinfunction "2_2") (pintype "passive"))
      (node (ref "R37") (pin "2") (pinfunction "2_2") (pintype "passive"))
      (node (ref "R4") (pin "1") (pinfunction "1_1") (pintype "passive"))
      (node (ref "RESET") (pin "P$1") (pinfunction "P$4_P$1") (pintype "bidirectional"))
      (node (ref "U1") (pin "106") (pinfunction "GND3_106") (pintype "power_in"))
      (node (ref "U1") (pin "12") (pinfunction "GND1_12") (pintype "power_in"))
      (node (ref "U1") (pin "126") (pinfunction "GND4_126") (pintype "power_in"))
      (node (ref "U1") (pin "33") (pinfunction "GNDPLL_33") (pintype "power_in"))
      (node (ref "U1") (pin "44") (pinfunction "GNDUTMI_44") (pintype "power_in"))
      (node (ref "U1") (pin "46") (pinfunction "JTAGSEL_46") (pintype "input"))
      (node (ref "U1") (pin "54") (pinfunction "GNDBU_54") (pintype "power_in"))
      (node (ref "U1") (pin "58") (pinfunction "GND2_58") (pintype "power_in"))
      (node (ref "U1") (pin "74") (pinfunction "GNDANA_74") (pintype "power_in"))
      (node (ref "U2") (pin "1") (pinfunction "ADJ_1") (pintype "input"))
      (node (ref "U3") (pin "4") (pinfunction "GND1_4") (pintype "passive"))
      (node (ref "U4") (pin "4") (pinfunction "GND1_4") (pintype "passive"))
      (node (ref "U5") (pin "4") (pinfunction "GND1_4") (pintype "passive"))
      (node (ref "U6") (pin "4") (pinfunction "GND1_4") (pintype "passive"))
      (node (ref "U7") (pin "PIN1") (pinfunction "NA1_PIN1") (pintype "bidirectional"))
      (node (ref "U7") (pin "PIN2") (pinfunction "NA2_PIN2") (pintype "bidirectional"))
      (node (ref "U7") (pin "PIN3") (pinfunction "E2_PIN3") (pintype "bidirectional"))
      (node (ref "U7") (pin "PIN4") (pinfunction "VSS_PIN4") (pintype "bidirectional"))
      (node (ref "U8") (pin "-VOUT") (pinfunction "-VOUT_-VOUT") (pintype "bidirectional"))
      (node (ref "WIFI") (pin "C") (pinfunction "C_C") (pintype "passive"))
      (node (ref "X1") (pin "4") (pinfunction "4_4") (pintype "passive"))
      (node (ref "Y1") (pin "2") (pinfunction "GND_2") (pintype "passive"))
      (node (ref "Y1") (pin "4") (pinfunction "GND_4") (pintype "passive"))
      (node (ref "Z1") (pin "2") (pinfunction "2_2") (pintype "passive"))
      (node (ref "Z2") (pin "2") (pinfunction "2_2") (pintype "passive"))
    )
    (net (code "76") (name "Net-(+3.3V-PadA)") (class "Default")
      (node (ref "+3.3V") (pin "A") (pinfunction "A_A") (pintype "passive"))
      (node (ref "R59") (pin "1") (pinfunction "1_1") (pintype "passive"))
    )
    (net (code "77") (name "Net-(+5V-PadA)") (class "Default")
      (node (ref "+5V") (pin "A") (pinfunction "A_A") (pintype "passive"))
      (node (ref "R58") (pin "1") (pinfunction "1_1") (pintype "passive"))
    )
    (net (code "78") (name "Net-(+12V-PadA)") (class "Default")
      (node (ref "+12V") (pin "A") (pinfunction "A_A") (pintype "passive"))
      (node (ref "R57") (pin "1") (pinfunction "1_1") (pintype "passive"))
    )
    (net (code "79") (name "Net-(C69-Pad1)") (class "Default")
      (node (ref "C69") (pin "1") (pinfunction "1_1") (pintype "passive"))
      (node (ref "R38") (pin "1") (pinfunction "1_1") (pintype "passive"))
      (node (ref "R39") (pin "1") (pinfunction "1_1") (pintype "passive"))
    )
    (net (code "80") (name "Net-(C72-Pad1)") (class "Default")
      (node (ref "C72") (pin "1") (pinfunction "1_1") (pintype "passive"))
      (node (ref "R40") (pin "1") (pinfunction "1_1") (pintype "passive"))
      (node (ref "R41") (pin "1") (pinfunction "1_1") (pintype "passive"))
    )
    (net (code "81") (name "Net-(ERASE-P$4)") (class "Default")
      (node (ref "ERASE") (pin "P$1") (pinfunction "P$4_P$1") (pintype "bidirectional"))
      (node (ref "U1") (pin "130") (pinfunction "PC0_130") (pintype "bidirectional"))
    )
    (net (code "82") (name "Net-(IC1-+IN)") (class "Default")
      (node (ref "C53") (pin "1") (pinfunction "1_1") (pintype "passive"))
      (node (ref "IC1") (pin "3") (pinfunction "+IN_3") (pintype "input"))
      (node (ref "R21") (pin "2") (pinfunction "2_2") (pintype "passive"))
      (node (ref "R24") (pin "1") (pinfunction "1_1") (pintype "passive"))
    )
    (net (code "83") (name "Net-(IC1--IN)") (class "Default")
      (node (ref "C43") (pin "2") (pinfunction "2_2") (pintype "passive"))
      (node (ref "IC1") (pin "2") (pinfunction "-IN_2") (pintype "input"))
      (node (ref "R14") (pin "1") (pinfunction "1_1") (pintype "passive"))
      (node (ref "R17") (pin "2") (pinfunction "2_2") (pintype "passive"))
    )
    (net (code "84") (name "Net-(IC2-+IN)") (class "Default")
      (node (ref "C54") (pin "1") (pinfunction "1_1") (pintype "passive"))
      (node (ref "IC2") (pin "3") (pinfunction "+IN_3") (pintype "input"))
      (node (ref "R23") (pin "2") (pinfunction "2_2") (pintype "passive"))
      (node (ref "R25") (pin "1") (pinfunction "1_1") (pintype "passive"))
    )
    (net (code "85") (name "Net-(IC2--IN)") (class "Default")
      (node (ref "C44") (pin "2") (pinfunction "2_2") (pintype "passive"))
      (node (ref "IC2") (pin "2") (pinfunction "-IN_2") (pintype "input"))
      (node (ref "R15") (pin "1") (pinfunction "1_1") (pintype "passive"))
      (node (ref "R19") (pin "2") (pinfunction "2_2") (pintype "passive"))
    )
    (net (code "86") (name "Net-(IC3-VIN)") (class "Default")
      (node (ref "C47") (pin "1") (pinfunction "1_1") (pintype "passive"))
      (node (ref "IC3") (pin "2") (pinfunction "VIN_2") (pintype "bidirectional"))
      (node (ref "R16") (pin "1") (pinfunction "1_1") (pintype "passive"))
      (node (ref "R20") (pin "2") (pinfunction "2_2") (pintype "passive"))
    )
    (net (code "87") (name "Net-(IC3-VOUT+)") (class "Default")
      (node (ref "IC3") (pin "7") (pinfunction "VOUT+_7") (pintype "bidirectional"))
      (node (ref "R21") (pin "1") (pinfunction "1_1") (pintype "passive"))
    )
    (net (code "88") (name "Net-(IC3-VOUT-)") (class "Default")
      (node (ref "IC3") (pin "6") (pinfunction "VOUT-_6") (pintype "bidirectional"))
      (node (ref "R17") (pin "1") (pinfunction "1_1") (pintype "passive"))
    )
    (net (code "89") (name "Net-(IC4-VIN)") (class "Default")
      (node (ref "C49") (pin "1") (pinfunction "1_1") (pintype "passive"))
      (node (ref "IC4") (pin "2") (pinfunction "VIN_2") (pintype "bidirectional"))
      (node (ref "R18") (pin "1") (pinfunction "1_1") (pintype "passive"))
      (node (ref "R22") (pin "2") (pinfunction "2_2") (pintype "passive"))
    )
    (net (code "90") (name "Net-(IC4-VOUT+)") (class "Default")
      (node (ref "IC4") (pin "7") (pinfunction "VOUT+_7") (pintype "bidirectional"))
      (node (ref "R23") (pin "1") (pinfunction "1_1") (pintype "passive"))
    )
    (net (code "91") (name "Net-(IC4-VOUT-)") (class "Default")
      (node (ref "IC4") (pin "6") (pinfunction "VOUT-_6") (pintype "bidirectional"))
      (node (ref "R19") (pin "1") (pinfunction "1_1") (pintype "passive"))
    )
    (net (code "92") (name "Net-(IC5-+IN)") (class "Default")
      (node (ref "C62") (pin "1") (pinfunction "1_1") (pintype "passive"))
      (node (ref "IC5") (pin "3") (pinfunction "+IN_3") (pintype "input"))
      (node (ref "R33") (pin "2") (pinfunction "2_2") (pintype "passive"))
      (node (ref "R36") (pin "1") (pinfunction "1_1") (pintype "passive"))
    )
    (net (code "93") (name "Net-(IC5--IN)") (class "Default")
      (node (ref "C55") (pin "2") (pinfunction "2_2") (pintype "passive"))
      (node (ref "IC5") (pin "2") (pinfunction "-IN_2") (pintype "input"))
      (node (ref "R26") (pin "1") (pinfunction "1_1") (pintype "passive"))
      (node (ref "R29") (pin "2") (pinfunction "2_2") (pintype "passive"))
    )
    (net (code "94") (name "Net-(IC6-+IN)") (class "Default")
      (node (ref "C66") (pin "1") (pinfunction "1_1") (pintype "passive"))
      (node (ref "IC6") (pin "3") (pinfunction "+IN_3") (pintype "input"))
      (node (ref "R35") (pin "2") (pinfunction "2_2") (pintype "passive"))
      (node (ref "R37") (pin "1") (pinfunction "1_1") (pintype "passive"))
    )
    (net (code "95") (name "Net-(IC6--IN)") (class "Default")
      (node (ref "C56") (pin "2") (pinfunction "2_2") (pintype "passive"))
      (node (ref "IC6") (pin "2") (pinfunction "-IN_2") (pintype "input"))
      (node (ref "R27") (pin "1") (pinfunction "1_1") (pintype "passive"))
      (node (ref "R31") (pin "2") (pinfunction "2_2") (pintype "passive"))
    )
    (net (code "96") (name "Net-(IC7-VIN)") (class "Default")
      (node (ref "C58") (pin "1") (pinfunction "1_1") (pintype "passive"))
      (node (ref "IC7") (pin "2") (pinfunction "VIN_2") (pintype "bidirectional"))
      (node (ref "R28") (pin "1") (pinfunction "1_1") (pintype "passive"))
      (node (ref "R32") (pin "2") (pinfunction "2_2") (pintype "passive"))
    )
    (net (code "97") (name "Net-(IC7-VOUT+)") (class "Default")
      (node (ref "IC7") (pin "7") (pinfunction "VOUT+_7") (pintype "bidirectional"))
      (node (ref "R33") (pin "1") (pinfunction "1_1") (pintype "passive"))
    )
    (net (code "98") (name "Net-(IC7-VOUT-)") (class "Default")
      (node (ref "IC7") (pin "6") (pinfunction "VOUT-_6") (pintype "bidirectional"))
      (node (ref "R29") (pin "1") (pinfunction "1_1") (pintype "passive"))
    )
    (net (code "99") (name "Net-(IC8-VIN)") (class "Default")
      (node (ref "C63") (pin "1") (pinfunction "1_1") (pintype "passive"))
      (node (ref "IC8") (pin "2") (pinfunction "VIN_2") (pintype "bidirectional"))
      (node (ref "R30") (pin "1") (pinfunction "1_1") (pintype "passive"))
      (node (ref "R34") (pin "2") (pinfunction "2_2") (pintype "passive"))
    )
    (net (code "100") (name "Net-(IC8-VOUT+)") (class "Default")
      (node (ref "IC8") (pin "7") (pinfunction "VOUT+_7") (pintype "bidirectional"))
      (node (ref "R35") (pin "1") (pinfunction "1_1") (pintype "passive"))
    )
    (net (code "101") (name "Net-(IC8-VOUT-)") (class "Default")
      (node (ref "IC8") (pin "6") (pinfunction "VOUT-_6") (pintype "bidirectional"))
      (node (ref "R31") (pin "1") (pinfunction "1_1") (pintype "passive"))
    )
    (net (code "102") (name "Net-(IWIFI-Pad5)") (class "Default")
      (node (ref "IWIFI") (pin "5") (pinfunction "5_5") (pintype "passive"))
      (node (ref "IWIFI") (pin "7") (pinfunction "7_7") (pintype "passive"))
    )
    (net (code "103") (name "Net-(IWIFI-Pad12)") (class "Default")
      (node (ref "IWIFI") (pin "12") (pinfunction "12_12") (pintype "passive"))
      (node (ref "R56") (pin "2") (pinfunction "2_2") (pintype "passive"))
    )
    (net (code "104") (name "Net-(LED-PadA)") (class "Default")
      (node (ref "LED") (pin "A") (pinfunction "A_A") (pintype "passive"))
      (node (ref "R5") (pin "1") (pinfunction "1_1") (pintype "passive"))
    )
    (net (code "105") (name "Net-(OK1A-A)") (class "Default")
      (node (ref "OK1") (pin "1") (pinfunction "A_1") (pintype "passive"))
      (node (ref "R44") (pin "2") (pinfunction "2_2") (pintype "passive"))
    )
    (net (code "106") (name "Net-(OK1A-COL)") (class "Default")
      (node (ref "OK1") (pin "8") (pinfunction "COL_8") (pintype "passive"))
      (node (ref "R45") (pin "1") (pinfunction "1_1") (pintype "passive"))
    )
    (net (code "107") (name "Net-(OK1B-A)") (class "Default")
      (node (ref "OK1") (pin "3") (pinfunction "A_3") (pintype "passive"))
      (node (ref "R46") (pin "2") (pinfunction "2_2") (pintype "passive"))
    )
    (net (code "108") (name "Net-(OK1B-COL)") (class "Default")
      (node (ref "OK1") (pin "6") (pinfunction "COL_6") (pintype "passive"))
      (node (ref "R47") (pin "1") (pinfunction "1_1") (pintype "passive"))
    )
    (net (code "109") (name "Net-(OK2A-A)") (class "Default")
      (node (ref "OK2") (pin "1") (pinfunction "A_1") (pintype "passive"))
      (node (ref "R50") (pin "2") (pinfunction "2_2") (pintype "passive"))
    )
    (net (code "110") (name "Net-(OK2A-COL)") (class "Default")
      (node (ref "OK2") (pin "8") (pinfunction "COL_8") (pintype "passive"))
      (node (ref "R51") (pin "1") (pinfunction "1_1") (pintype "passive"))
    )
    (net (code "111") (name "Net-(OK2B-A)") (class "Default")
      (node (ref "OK2") (pin "3") (pinfunction "A_3") (pintype "passive"))
      (node (ref "R52") (pin "2") (pinfunction "2_2") (pintype "passive"))
    )
    (net (code "112") (name "Net-(OK2B-COL)") (class "Default")
      (node (ref "OK2") (pin "6") (pinfunction "COL_6") (pintype "passive"))
      (node (ref "R53") (pin "1") (pinfunction "1_1") (pintype "passive"))
    )
    (net (code "113") (name "Net-(PTC-2)") (class "Default")
      (node (ref "D9") (pin "C") (pinfunction "C_C") (pintype "passive"))
      (node (ref "PTC") (pin "P$2") (pinfunction "2_P$2") (pintype "passive"))
      (node (ref "TVS") (pin "C") (pinfunction "C_C") (pintype "passive"))
      (node (ref "ZEN") (pin "C") (pinfunction "C_C") (pintype "passive"))
    )
    (net (code "114") (name "Net-(R38-Pad2)") (class "Default")
      (node (ref "R38") (pin "2") (pinfunction "2_2") (pintype "passive"))
      (node (ref "SJ1") (pin "2") (pinfunction "2_2") (pintype "passive"))
    )
    (net (code "115") (name "Net-(R39-Pad2)") (class "Default")
      (node (ref "R39") (pin "2") (pinfunction "2_2") (pintype "passive"))
      (node (ref "SJ2") (pin "2") (pinfunction "2_2") (pintype "passive"))
    )
    (net (code "116") (name "Net-(R40-Pad2)") (class "Default")
      (node (ref "R40") (pin "2") (pinfunction "2_2") (pintype "passive"))
      (node (ref "SJ3") (pin "2") (pinfunction "2_2") (pintype "passive"))
    )
    (net (code "117") (name "Net-(R41-Pad2)") (class "Default")
      (node (ref "R41") (pin "2") (pinfunction "2_2") (pintype "passive"))
      (node (ref "SJ4") (pin "2") (pinfunction "2_2") (pintype "passive"))
    )
    (net (code "118") (name "Net-(R56-Pad1)") (class "Default")
      (node (ref "R56") (pin "1") (pinfunction "1_1") (pintype "passive"))
      (node (ref "WIFI") (pin "A") (pinfunction "A_A") (pintype "passive"))
    )
    (net (code "119") (name "Net-(U1-DFSDM)") (class "Default")
      (node (ref "R2") (pin "2") (pinfunction "2_2") (pintype "passive"))
      (node (ref "U1") (pin "43") (pinfunction "DFSDM_43") (pintype "input"))
    )
    (net (code "120") (name "Net-(U1-DFSDP)") (class "Default")
      (node (ref "R3") (pin "2") (pinfunction "2_2") (pintype "passive"))
      (node (ref "U1") (pin "42") (pinfunction "DFSDP_42") (pintype "input"))
    )
    (net (code "121") (name "Net-(U1-FWUP)") (class "Default")
      (node (ref "R1") (pin "1") (pinfunction "1_1") (pintype "passive"))
      (node (ref "U1") (pin "53") (pinfunction "FWUP_53") (pintype "input"))
    )
    (net (code "122") (name "unconnected-(IC1-NC-Pad8)") (class "Default")
      (node (ref "IC1") (pin "8") (pinfunction "NC_8") (pintype "no_connect"))
    )
    (net (code "123") (name "unconnected-(IC1-REF-Pad1)") (class "Default")
      (node (ref "IC1") (pin "1") (pinfunction "REF_1") (pintype "passive"))
    )
    (net (code "124") (name "unconnected-(IC1-SENSE-Pad5)") (class "Default")
      (node (ref "IC1") (pin "5") (pinfunction "SENSE_5") (pintype "passive"))
    )
    (net (code "125") (name "unconnected-(IC2-NC-Pad8)") (class "Default")
      (node (ref "IC2") (pin "8") (pinfunction "NC_8") (pintype "no_connect"))
    )
    (net (code "126") (name "unconnected-(IC2-REF-Pad1)") (class "Default")
      (node (ref "IC2") (pin "1") (pinfunction "REF_1") (pintype "passive"))
    )
    (net (code "127") (name "unconnected-(IC2-SENSE-Pad5)") (class "Default")
      (node (ref "IC2") (pin "5") (pinfunction "SENSE_5") (pintype "passive"))
    )
    (net (code "128") (name "unconnected-(IC5-NC-Pad8)") (class "Default")
      (node (ref "IC5") (pin "8") (pinfunction "NC_8") (pintype "no_connect"))
    )
    (net (code "129") (name "unconnected-(IC5-REF-Pad1)") (class "Default")
      (node (ref "IC5") (pin "1") (pinfunction "REF_1") (pintype "passive"))
    )
    (net (code "130") (name "unconnected-(IC5-SENSE-Pad5)") (class "Default")
      (node (ref "IC5") (pin "5") (pinfunction "SENSE_5") (pintype "passive"))
    )
    (net (code "131") (name "unconnected-(IC6-NC-Pad8)") (class "Default")
      (node (ref "IC6") (pin "8") (pinfunction "NC_8") (pintype "no_connect"))
    )
    (net (code "132") (name "unconnected-(IC6-REF-Pad1)") (class "Default")
      (node (ref "IC6") (pin "1") (pinfunction "REF_1") (pintype "passive"))
    )
    (net (code "133") (name "unconnected-(IC6-SENSE-Pad5)") (class "Default")
      (node (ref "IC6") (pin "5") (pinfunction "SENSE_5") (pintype "passive"))
    )
    (net (code "134") (name "unconnected-(IC9-NC-Pad4)") (class "Default")
      (node (ref "IC9") (pin "4") (pinfunction "NC_4") (pintype "input"))
    )
    (net (code "135") (name "unconnected-(IC9-NC-Pad5)") (class "Default")
      (node (ref "IC9") (pin "5") (pinfunction "NC_5") (pintype "input"))
    )
    (net (code "136") (name "unconnected-(IC9-NC-Pad11)") (class "Default")
      (node (ref "IC9") (pin "11") (pinfunction "NC_11") (pintype "input"))
    )
    (net (code "137") (name "unconnected-(IC9-NC-Pad14)") (class "Default")
      (node (ref "IC9") (pin "14") (pinfunction "NC_14") (pintype "input"))
    )
    (net (code "138") (name "unconnected-(IC10-NC-Pad4)") (class "Default")
      (node (ref "IC10") (pin "4") (pinfunction "NC_4") (pintype "input"))
    )
    (net (code "139") (name "unconnected-(IC10-NC-Pad5)") (class "Default")
      (node (ref "IC10") (pin "5") (pinfunction "NC_5") (pintype "input"))
    )
    (net (code "140") (name "unconnected-(IC10-NC-Pad11)") (class "Default")
      (node (ref "IC10") (pin "11") (pinfunction "NC_11") (pintype "input"))
    )
    (net (code "141") (name "unconnected-(IC10-NC-Pad14)") (class "Default")
      (node (ref "IC10") (pin "14") (pinfunction "NC_14") (pintype "input"))
    )
    (net (code "142") (name "unconnected-(IWIFI-Pad6)") (class "Default")
      (node (ref "IWIFI") (pin "6") (pinfunction "6_6") (pintype "passive"))
    )
    (net (code "143") (name "unconnected-(IWIFI-Pad8)") (class "Default")
      (node (ref "IWIFI") (pin "8") (pinfunction "8_8") (pintype "passive"))
    )
    (net (code "144") (name "unconnected-(IWIFI-Pad9)") (class "Default")
      (node (ref "IWIFI") (pin "9") (pinfunction "9_9") (pintype "passive"))
    )
    (net (code "145") (name "unconnected-(U1-NRST-Pad69)") (class "Default")
      (node (ref "U1") (pin "69") (pinfunction "NRST_69") (pintype "bidirectional"))
    )
    (net (code "146") (name "unconnected-(U1-PA2-Pad85)") (class "Default")
      (node (ref "U1") (pin "85") (pinfunction "PA2_85") (pintype "bidirectional"))
    )
    (net (code "147") (name "unconnected-(U1-PA3-Pad84)") (class "Default")
      (node (ref "U1") (pin "84") (pinfunction "PA3_84") (pintype "bidirectional"))
    )
    (net (code "148") (name "unconnected-(U1-PA4-Pad83)") (class "Default")
      (node (ref "U1") (pin "83") (pinfunction "PA4_83") (pintype "bidirectional"))
    )
    (net (code "149") (name "unconnected-(U1-PA5-Pad25)") (class "Default")
      (node (ref "U1") (pin "25") (pinfunction "PA5_25") (pintype "bidirectional"))
    )
    (net (code "150") (name "unconnected-(U1-PA6-Pad82)") (class "Default")
      (node (ref "U1") (pin "82") (pinfunction "PA6_82") (pintype "bidirectional"))
    )
    (net (code "151") (name "unconnected-(U1-PA7-Pad26)") (class "Default")
      (node (ref "U1") (pin "26") (pinfunction "PA7_26") (pintype "bidirectional"))
    )
    (net (code "152") (name "unconnected-(U1-PA8-Pad27)") (class "Default")
      (node (ref "U1") (pin "27") (pinfunction "PA8_27") (pintype "bidirectional"))
    )
    (net (code "153") (name "unconnected-(U1-PA9-Pad2)") (class "Default")
      (node (ref "U1") (pin "2") (pinfunction "PA9_2") (pintype "bidirectional"))
    )
    (net (code "154") (name "unconnected-(U1-PA10-Pad3)") (class "Default")
      (node (ref "U1") (pin "3") (pinfunction "PA10_3") (pintype "bidirectional"))
    )
    (net (code "155") (name "unconnected-(U1-PA14-Pad7)") (class "Default")
      (node (ref "U1") (pin "7") (pinfunction "PA14_7") (pintype "bidirectional"))
    )
    (net (code "156") (name "unconnected-(U1-PA15-Pad8)") (class "Default")
      (node (ref "U1") (pin "8") (pinfunction "PA15_8") (pintype "bidirectional"))
    )
    (net (code "157") (name "unconnected-(U1-PA17-Pad9)") (class "Default")
      (node (ref "U1") (pin "9") (pinfunction "PA17_9") (pintype "bidirectional"))
    )
    (net (code "158") (name "unconnected-(U1-PA18-Pad70)") (class "Default")
      (node (ref "U1") (pin "70") (pinfunction "PA18_70") (pintype "bidirectional"))
    )
    (net (code "159") (name "unconnected-(U1-PA20-Pad72)") (class "Default")
      (node (ref "U1") (pin "72") (pinfunction "PA20_72") (pintype "bidirectional"))
    )
    (net (code "160") (name "unconnected-(U1-PA21-Pad107)") (class "Default")
      (node (ref "U1") (pin "107") (pinfunction "PA21_107") (pintype "bidirectional"))
    )
    (net (code "161") (name "unconnected-(U1-PA25-Pad108)") (class "Default")
      (node (ref "U1") (pin "108") (pinfunction "PA25_108") (pintype "bidirectional"))
    )
    (net (code "162") (name "unconnected-(U1-PA26-Pad109)") (class "Default")
      (node (ref "U1") (pin "109") (pinfunction "PA26_109") (pintype "bidirectional"))
    )
    (net (code "163") (name "unconnected-(U1-PA27-Pad110)") (class "Default")
      (node (ref "U1") (pin "110") (pinfunction "PA27_110") (pintype "bidirectional"))
    )
    (net (code "164") (name "unconnected-(U1-PA28-Pad111)") (class "Default")
      (node (ref "U1") (pin "111") (pinfunction "PA28_111") (pintype "bidirectional"))
    )
    (net (code "165") (name "unconnected-(U1-PA29-Pad112)") (class "Default")
      (node (ref "U1") (pin "112") (pinfunction "PA29_112") (pintype "bidirectional"))
    )
    (net (code "166") (name "unconnected-(U1-PB0-Pad113)") (class "Default")
      (node (ref "U1") (pin "113") (pinfunction "PB0_113") (pintype "bidirectional"))
    )
    (net (code "167") (name "unconnected-(U1-PB1-Pad114)") (class "Default")
      (node (ref "U1") (pin "114") (pinfunction "PB1_114") (pintype "bidirectional"))
    )
    (net (code "168") (name "unconnected-(U1-PB2-Pad115)") (class "Default")
      (node (ref "U1") (pin "115") (pinfunction "PB2_115") (pintype "bidirectional"))
    )
    (net (code "169") (name "unconnected-(U1-PB3-Pad118)") (class "Default")
      (node (ref "U1") (pin "118") (pinfunction "PB3_118") (pintype "bidirectional"))
    )
    (net (code "170") (name "unconnected-(U1-PB4-Pad119)") (class "Default")
      (node (ref "U1") (pin "119") (pinfunction "PB4_119") (pintype "bidirectional"))
    )
    (net (code "171") (name "unconnected-(U1-PB5-Pad120)") (class "Default")
      (node (ref "U1") (pin "120") (pinfunction "PB5_120") (pintype "bidirectional"))
    )
    (net (code "172") (name "unconnected-(U1-PB6-Pad121)") (class "Default")
      (node (ref "U1") (pin "121") (pinfunction "PB6_121") (pintype "bidirectional"))
    )
    (net (code "173") (name "unconnected-(U1-PB7-Pad122)") (class "Default")
      (node (ref "U1") (pin "122") (pinfunction "PB7_122") (pintype "bidirectional"))
    )
    (net (code "174") (name "unconnected-(U1-PB8-Pad123)") (class "Default")
      (node (ref "U1") (pin "123") (pinfunction "PB8_123") (pintype "bidirectional"))
    )
    (net (code "175") (name "unconnected-(U1-PB9-Pad127)") (class "Default")
      (node (ref "U1") (pin "127") (pinfunction "PB9_127") (pintype "bidirectional"))
    )
    (net (code "176") (name "unconnected-(U1-PB10-Pad128)") (class "Default")
      (node (ref "U1") (pin "128") (pinfunction "PB10_128") (pintype "bidirectional"))
    )
    (net (code "177") (name "unconnected-(U1-PB11-Pad129)") (class "Default")
      (node (ref "U1") (pin "129") (pinfunction "PB11_129") (pintype "bidirectional"))
    )
    (net (code "178") (name "unconnected-(U1-PB16-Pad77)") (class "Default")
      (node (ref "U1") (pin "77") (pinfunction "PB16_77") (pintype "bidirectional"))
    )
    (net (code "179") (name "unconnected-(U1-PB17-Pad88)") (class "Default")
      (node (ref "U1") (pin "88") (pinfunction "PB17_88") (pintype "bidirectional"))
    )
    (net (code "180") (name "unconnected-(U1-PB18-Pad89)") (class "Default")
      (node (ref "U1") (pin "89") (pinfunction "PB18_89") (pintype "bidirectional"))
    )
    (net (code "181") (name "unconnected-(U1-PB19-Pad90)") (class "Default")
      (node (ref "U1") (pin "90") (pinfunction "PB19_90") (pintype "bidirectional"))
    )
    (net (code "182") (name "unconnected-(U1-PB20-Pad91)") (class "Default")
      (node (ref "U1") (pin "91") (pinfunction "PB20_91") (pintype "bidirectional"))
    )
    (net (code "183") (name "unconnected-(U1-PB21-Pad92)") (class "Default")
      (node (ref "U1") (pin "92") (pinfunction "PB21_92") (pintype "bidirectional"))
    )
    (net (code "184") (name "unconnected-(U1-PB22-Pad141)") (class "Default")
      (node (ref "U1") (pin "141") (pinfunction "PB22_141") (pintype "bidirectional"))
    )
    (net (code "185") (name "unconnected-(U1-PB23-Pad142)") (class "Default")
      (node (ref "U1") (pin "142") (pinfunction "PB23_142") (pintype "bidirectional"))
    )
    (net (code "186") (name "unconnected-(U1-PB24-Pad143)") (class "Default")
      (node (ref "U1") (pin "143") (pinfunction "PB24_143") (pintype "bidirectional"))
    )
    (net (code "187") (name "unconnected-(U1-PB26-Pad1)") (class "Default")
      (node (ref "U1") (pin "1") (pinfunction "PB26_1") (pintype "bidirectional"))
    )
    (net (code "188") (name "unconnected-(U1-PB28-Pad28)") (class "Default")
      (node (ref "U1") (pin "28") (pinfunction "PB28_28") (pintype "bidirectional"))
    )
    (net (code "189") (name "unconnected-(U1-PB29-Pad29)") (class "Default")
      (node (ref "U1") (pin "29") (pinfunction "PB29_29") (pintype "bidirectional"))
    )
    (net (code "190") (name "unconnected-(U1-PB30-Pad30)") (class "Default")
      (node (ref "U1") (pin "30") (pinfunction "PB30_30") (pintype "bidirectional"))
    )
    (net (code "191") (name "unconnected-(U1-PB31-Pad31)") (class "Default")
      (node (ref "U1") (pin "31") (pinfunction "PB31_31") (pintype "bidirectional"))
    )
    (net (code "192") (name "unconnected-(U1-PC1-Pad55)") (class "Default")
      (node (ref "U1") (pin "55") (pinfunction "PC1_55") (pintype "bidirectional"))
    )
    (net (code "193") (name "unconnected-(U1-PC2-Pad59)") (class "Default")
      (node (ref "U1") (pin "59") (pinfunction "PC2_59") (pintype "bidirectional"))
    )
    (net (code "194") (name "unconnected-(U1-PC3-Pad60)") (class "Default")
      (node (ref "U1") (pin "60") (pinfunction "PC3_60") (pintype "bidirectional"))
    )
    (net (code "195") (name "unconnected-(U1-PC4-Pad116)") (class "Default")
      (node (ref "U1") (pin "116") (pinfunction "PC4_116") (pintype "bidirectional"))
    )
    (net (code "196") (name "unconnected-(U1-PC5-Pad63)") (class "Default")
      (node (ref "U1") (pin "63") (pinfunction "PC5_63") (pintype "bidirectional"))
    )
    (net (code "197") (name "unconnected-(U1-PC6-Pad64)") (class "Default")
      (node (ref "U1") (pin "64") (pinfunction "PC6_64") (pintype "bidirectional"))
    )
    (net (code "198") (name "unconnected-(U1-PC7-Pad65)") (class "Default")
      (node (ref "U1") (pin "65") (pinfunction "PC7_65") (pintype "bidirectional"))
    )
    (net (code "199") (name "unconnected-(U1-PC8-Pad66)") (class "Default")
      (node (ref "U1") (pin "66") (pinfunction "PC8_66") (pintype "bidirectional"))
    )
    (net (code "200") (name "unconnected-(U1-PC9-Pad67)") (class "Default")
      (node (ref "U1") (pin "67") (pinfunction "PC9_67") (pintype "bidirectional"))
    )
    (net (code "201") (name "unconnected-(U1-PC10-Pad117)") (class "Default")
      (node (ref "U1") (pin "117") (pinfunction "PC10_117") (pintype "bidirectional"))
    )
    (net (code "202") (name "unconnected-(U1-PC11-Pad93)") (class "Default")
      (node (ref "U1") (pin "93") (pinfunction "PC11_93") (pintype "bidirectional"))
    )
    (net (code "203") (name "unconnected-(U1-PC16-Pad98)") (class "Default")
      (node (ref "U1") (pin "98") (pinfunction "PC16_98") (pintype "bidirectional"))
    )
    (net (code "204") (name "unconnected-(U1-PC17-Pad99)") (class "Default")
      (node (ref "U1") (pin "99") (pinfunction "PC17_99") (pintype "bidirectional"))
    )
    (net (code "205") (name "unconnected-(U1-PC18-Pad100)") (class "Default")
      (node (ref "U1") (pin "100") (pinfunction "PC18_100") (pintype "bidirectional"))
    )
    (net (code "206") (name "unconnected-(U1-PC19-Pad101)") (class "Default")
      (node (ref "U1") (pin "101") (pinfunction "PC19_101") (pintype "bidirectional"))
    )
    (net (code "207") (name "unconnected-(U1-PC20-Pad131)") (class "Default")
      (node (ref "U1") (pin "131") (pinfunction "PC20_131") (pintype "bidirectional"))
    )
    (net (code "208") (name "unconnected-(U1-PC27-Pad138)") (class "Default")
      (node (ref "U1") (pin "138") (pinfunction "PC27_138") (pintype "bidirectional"))
    )
    (net (code "209") (name "unconnected-(U1-PC29-Pad102)") (class "Default")
      (node (ref "U1") (pin "102") (pinfunction "PC29_102") (pintype "bidirectional"))
    )
    (net (code "210") (name "unconnected-(U1-PC30-Pad103)") (class "Default")
      (node (ref "U1") (pin "103") (pinfunction "PC30_103") (pintype "bidirectional"))
    )
    (net (code "211") (name "unconnected-(U1-PD0-Pad13)") (class "Default")
      (node (ref "U1") (pin "13") (pinfunction "PD0_13") (pintype "bidirectional"))
    )
    (net (code "212") (name "unconnected-(U1-PD1-Pad14)") (class "Default")
      (node (ref "U1") (pin "14") (pinfunction "PD1_14") (pintype "bidirectional"))
    )
    (net (code "213") (name "unconnected-(U1-PD2-Pad15)") (class "Default")
      (node (ref "U1") (pin "15") (pinfunction "PD2_15") (pintype "bidirectional"))
    )
    (net (code "214") (name "unconnected-(U1-PD3-Pad16)") (class "Default")
      (node (ref "U1") (pin "16") (pinfunction "PD3_16") (pintype "bidirectional"))
    )
    (net (code "215") (name "unconnected-(U1-PD4-Pad17)") (class "Default")
      (node (ref "U1") (pin "17") (pinfunction "PD4_17") (pintype "bidirectional"))
    )
    (net (code "216") (name "unconnected-(U1-PD5-Pad18)") (class "Default")
      (node (ref "U1") (pin "18") (pinfunction "PD5_18") (pintype "bidirectional"))
    )
    (net (code "217") (name "unconnected-(U1-PD6-Pad19)") (class "Default")
      (node (ref "U1") (pin "19") (pinfunction "PD6_19") (pintype "bidirectional"))
    )
    (net (code "218") (name "unconnected-(U1-PD7-Pad20)") (class "Default")
      (node (ref "U1") (pin "20") (pinfunction "PD7_20") (pintype "bidirectional"))
    )
    (net (code "219") (name "unconnected-(U1-PD8-Pad21)") (class "Default")
      (node (ref "U1") (pin "21") (pinfunction "PD8_21") (pintype "bidirectional"))
    )
    (net (code "220") (name "unconnected-(U1-PD9-Pad22)") (class "Default")
      (node (ref "U1") (pin "22") (pinfunction "PD9_22") (pintype "bidirectional"))
    )
    (net (code "221") (name "unconnected-(U1-PD10-Pad32)") (class "Default")
      (node (ref "U1") (pin "32") (pinfunction "PD10_32") (pintype "bidirectional"))
    )
    (net (code "222") (name "unconnected-(U1-SHDN-Pad50)") (class "Default")
      (node (ref "U1") (pin "50") (pinfunction "SHDN_50") (pintype "output"))
    )
    (net (code "223") (name "unconnected-(U1-TST-Pad51)") (class "Default")
      (node (ref "U1") (pin "51") (pinfunction "TST_51") (pintype "input"))
    )
    (net (code "224") (name "unconnected-(U7-WC-PadPIN7)") (class "Default")
      (node (ref "U7") (pin "PIN7") (pinfunction "WC_PIN7") (pintype "bidirectional"))
    )
    (net (code "225") (name "unconnected-(X1-PadS1)") (class "Default")
      (node (ref "X1") (pin "S1") (pinfunction "S1_S1") (pintype "passive"))
    )
    (net (code "226") (name "unconnected-(X1-PadS2)") (class "Default")
      (node (ref "X1") (pin "S2") (pinfunction "S2_S2") (pintype "passive"))
    )
  )
)
